# muneeb_v3.net
KiCad netlist of a schematic drawn in EAGLE
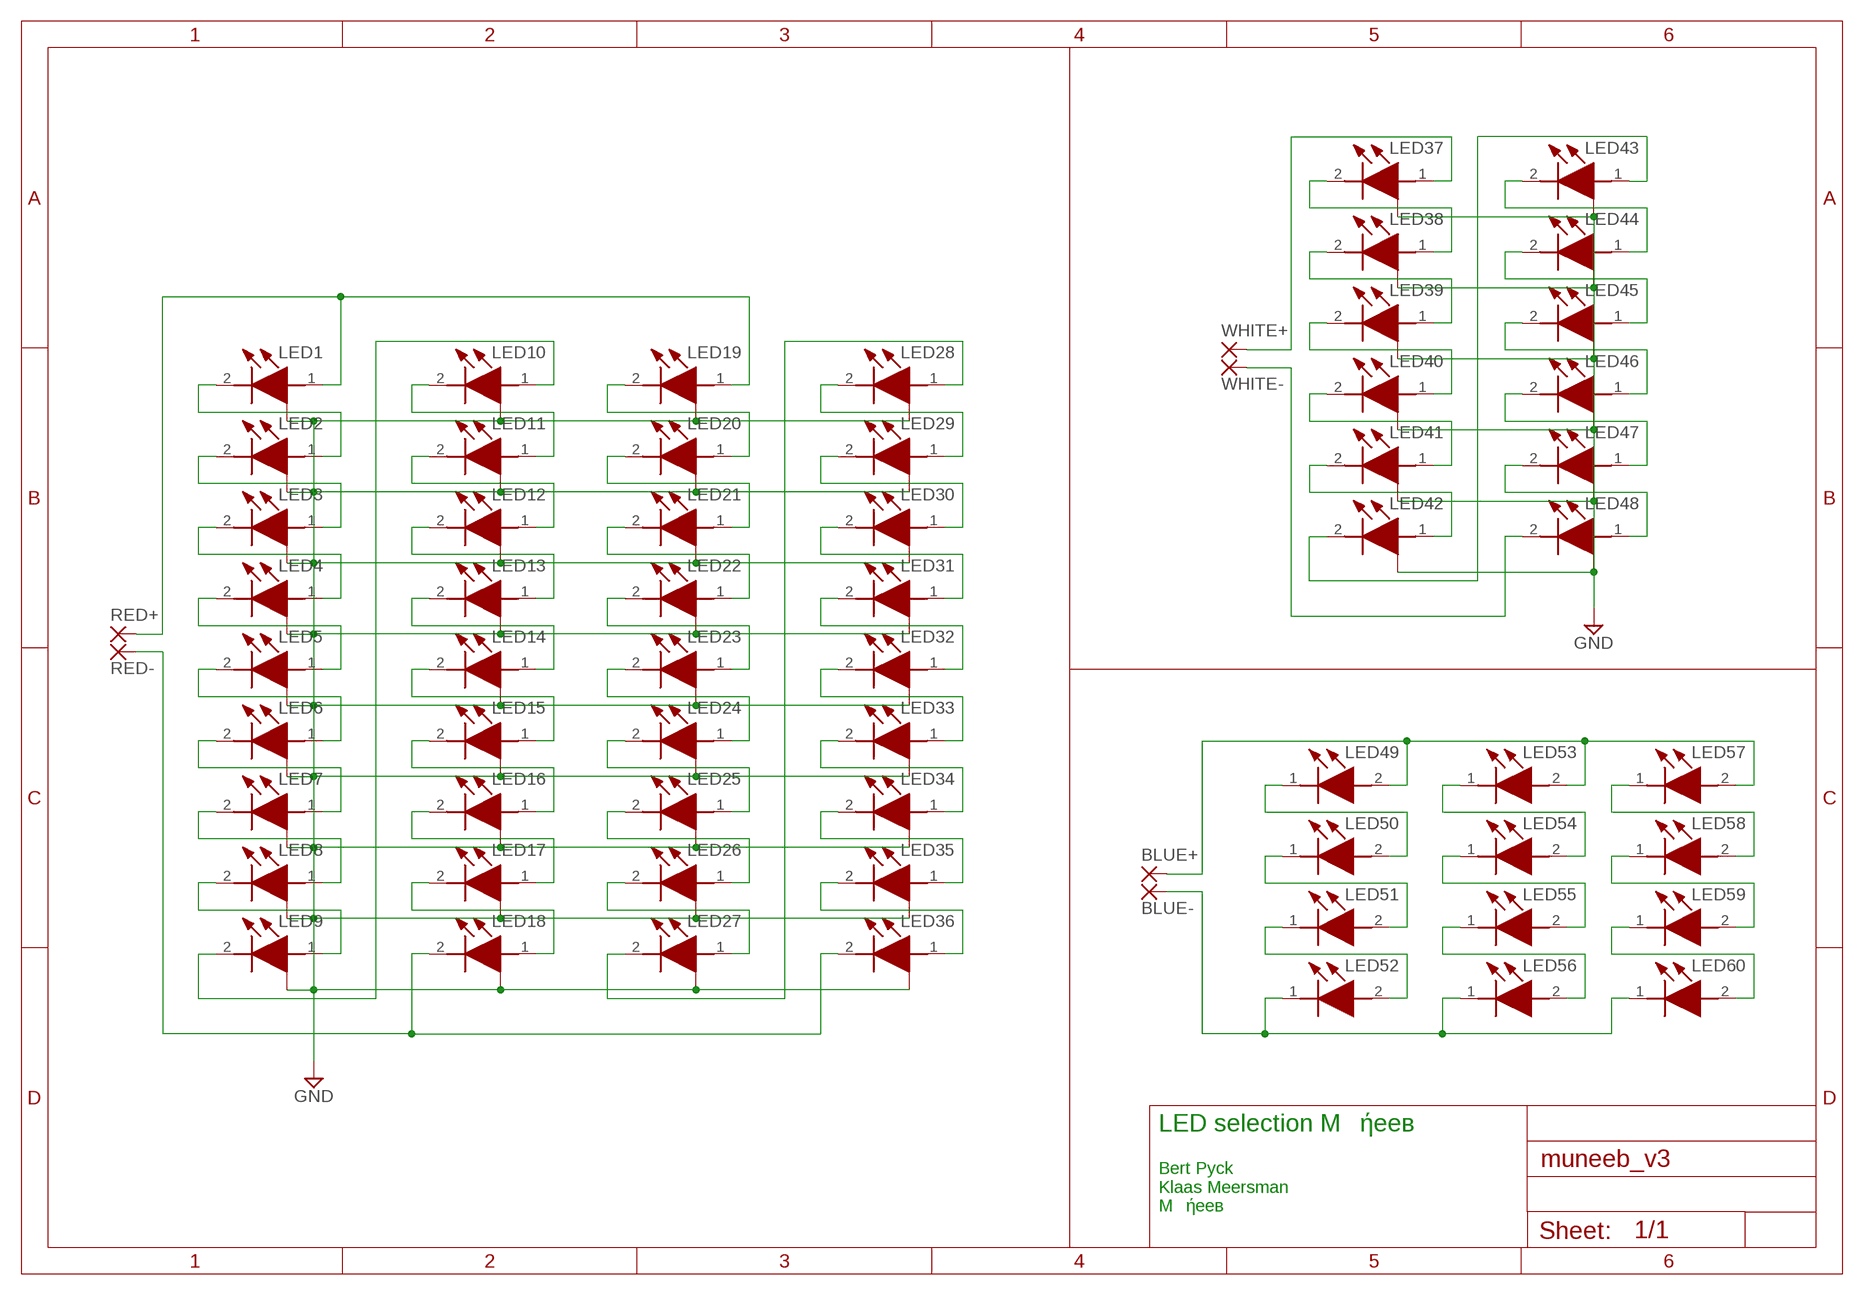
[diagram p0: schematic, sheet 1]

(export (version "E")
  (design (tool "Eeschema 10.0.6"))
  (components
    (comp (ref "BLUE+")
      (value "SOLDERPAD")
      (footprint "eagle-import:SOLDERPAD")
      (libsource (lib "eagle-import") (part "SOLDERPAD"))
    )
    (comp (ref "BLUE-")
      (value "SOLDERPAD")
      (footprint "eagle-import:SOLDERPAD")
      (libsource (lib "eagle-import") (part "SOLDERPAD"))
    )
    (comp (ref "LED1")
      (value "RED")
      (footprint "eagle-import:GR_CSSRML.24")
      (libsource (lib "eagle-import") (part "RED"))
    )
    (comp (ref "LED2")
      (value "RED")
      (footprint "eagle-import:GR_CSSRML.24")
      (libsource (lib "eagle-import") (part "RED"))
    )
    (comp (ref "LED3")
      (value "RED")
      (footprint "eagle-import:GR_CSSRML.24")
      (libsource (lib "eagle-import") (part "RED"))
    )
    (comp (ref "LED4")
      (value "RED")
      (footprint "eagle-import:GR_CSSRML.24")
      (libsource (lib "eagle-import") (part "RED"))
    )
    (comp (ref "LED5")
      (value "RED")
      (footprint "eagle-import:GR_CSSRML.24")
      (libsource (lib "eagle-import") (part "RED"))
    )
    (comp (ref "LED6")
      (value "RED")
      (footprint "eagle-import:GR_CSSRML.24")
      (libsource (lib "eagle-import") (part "RED"))
    )
    (comp (ref "LED7")
      (value "RED")
      (footprint "eagle-import:GR_CSSRML.24")
      (libsource (lib "eagle-import") (part "RED"))
    )
    (comp (ref "LED8")
      (value "RED")
      (footprint "eagle-import:GR_CSSRML.24")
      (libsource (lib "eagle-import") (part "RED"))
    )
    (comp (ref "LED9")
      (value "RED")
      (footprint "eagle-import:GR_CSSRML.24")
      (libsource (lib "eagle-import") (part "RED"))
    )
    (comp (ref "LED10")
      (value "RED")
      (footprint "eagle-import:GR_CSSRML.24")
      (libsource (lib "eagle-import") (part "RED"))
    )
    (comp (ref "LED11")
      (value "RED")
      (footprint "eagle-import:GR_CSSRML.24")
      (libsource (lib "eagle-import") (part "RED"))
    )
    (comp (ref "LED12")
      (value "RED")
      (footprint "eagle-import:GR_CSSRML.24")
      (libsource (lib "eagle-import") (part "RED"))
    )
    (comp (ref "LED13")
      (value "RED")
      (footprint "eagle-import:GR_CSSRML.24")
      (libsource (lib "eagle-import") (part "RED"))
    )
    (comp (ref "LED14")
      (value "RED")
      (footprint "eagle-import:GR_CSSRML.24")
      (libsource (lib "eagle-import") (part "RED"))
    )
    (comp (ref "LED15")
      (value "RED")
      (footprint "eagle-import:GR_CSSRML.24")
      (libsource (lib "eagle-import") (part "RED"))
    )
    (comp (ref "LED16")
      (value "RED")
      (footprint "eagle-import:GR_CSSRML.24")
      (libsource (lib "eagle-import") (part "RED"))
    )
    (comp (ref "LED17")
      (value "RED")
      (footprint "eagle-import:GR_CSSRML.24")
      (libsource (lib "eagle-import") (part "RED"))
    )
    (comp (ref "LED18")
      (value "RED")
      (footprint "eagle-import:GR_CSSRML.24")
      (libsource (lib "eagle-import") (part "RED"))
    )
    (comp (ref "LED19")
      (value "RED")
      (footprint "eagle-import:GR_CSSRML.24")
      (libsource (lib "eagle-import") (part "RED"))
    )
    (comp (ref "LED20")
      (value "RED")
      (footprint "eagle-import:GR_CSSRML.24")
      (libsource (lib "eagle-import") (part "RED"))
    )
    (comp (ref "LED21")
      (value "RED")
      (footprint "eagle-import:GR_CSSRML.24")
      (libsource (lib "eagle-import") (part "RED"))
    )
    (comp (ref "LED22")
      (value "RED")
      (footprint "eagle-import:GR_CSSRML.24")
      (libsource (lib "eagle-import") (part "RED"))
    )
    (comp (ref "LED23")
      (value "RED")
      (footprint "eagle-import:GR_CSSRML.24")
      (libsource (lib "eagle-import") (part "RED"))
    )
    (comp (ref "LED24")
      (value "RED")
      (footprint "eagle-import:GR_CSSRML.24")
      (libsource (lib "eagle-import") (part "RED"))
    )
    (comp (ref "LED25")
      (value "RED")
      (footprint "eagle-import:GR_CSSRML.24")
      (libsource (lib "eagle-import") (part "RED"))
    )
    (comp (ref "LED26")
      (value "RED")
      (footprint "eagle-import:GR_CSSRML.24")
      (libsource (lib "eagle-import") (part "RED"))
    )
    (comp (ref "LED27")
      (value "RED")
      (footprint "eagle-import:GR_CSSRML.24")
      (libsource (lib "eagle-import") (part "RED"))
    )
    (comp (ref "LED28")
      (value "RED")
      (footprint "eagle-import:GR_CSSRML.24")
      (libsource (lib "eagle-import") (part "RED"))
    )
    (comp (ref "LED29")
      (value "RED")
      (footprint "eagle-import:GR_CSSRML.24")
      (libsource (lib "eagle-import") (part "RED"))
    )
    (comp (ref "LED30")
      (value "RED")
      (footprint "eagle-import:GR_CSSRML.24")
      (libsource (lib "eagle-import") (part "RED"))
    )
    (comp (ref "LED31")
      (value "RED")
      (footprint "eagle-import:GR_CSSRML.24")
      (libsource (lib "eagle-import") (part "RED"))
    )
    (comp (ref "LED32")
      (value "RED")
      (footprint "eagle-import:GR_CSSRML.24")
      (libsource (lib "eagle-import") (part "RED"))
    )
    (comp (ref "LED33")
      (value "RED")
      (footprint "eagle-import:GR_CSSRML.24")
      (libsource (lib "eagle-import") (part "RED"))
    )
    (comp (ref "LED34")
      (value "RED")
      (footprint "eagle-import:GR_CSSRML.24")
      (libsource (lib "eagle-import") (part "RED"))
    )
    (comp (ref "LED35")
      (value "RED")
      (footprint "eagle-import:GR_CSSRML.24")
      (libsource (lib "eagle-import") (part "RED"))
    )
    (comp (ref "LED36")
      (value "RED")
      (footprint "eagle-import:GR_CSSRML.24")
      (libsource (lib "eagle-import") (part "RED"))
    )
    (comp (ref "LED37")
      (value "WHITE")
      (footprint "eagle-import:GR_CSSRML.24")
      (libsource (lib "eagle-import") (part "WHITE"))
    )
    (comp (ref "LED38")
      (value "WHITE")
      (footprint "eagle-import:GR_CSSRML.24")
      (libsource (lib "eagle-import") (part "WHITE"))
    )
    (comp (ref "LED39")
      (value "WHITE")
      (footprint "eagle-import:GR_CSSRML.24")
      (libsource (lib "eagle-import") (part "WHITE"))
    )
    (comp (ref "LED40")
      (value "WHITE")
      (footprint "eagle-import:GR_CSSRML.24")
      (libsource (lib "eagle-import") (part "WHITE"))
    )
    (comp (ref "LED41")
      (value "WHITE")
      (footprint "eagle-import:GR_CSSRML.24")
      (libsource (lib "eagle-import") (part "WHITE"))
    )
    (comp (ref "LED42")
      (value "WHITE")
      (footprint "eagle-import:GR_CSSRML.24")
      (libsource (lib "eagle-import") (part "WHITE"))
    )
    (comp (ref "LED43")
      (value "WHITE")
      (footprint "eagle-import:GR_CSSRML.24")
      (libsource (lib "eagle-import") (part "WHITE"))
    )
    (comp (ref "LED44")
      (value "WHITE")
      (footprint "eagle-import:GR_CSSRML.24")
      (libsource (lib "eagle-import") (part "WHITE"))
    )
    (comp (ref "LED45")
      (value "WHITE")
      (footprint "eagle-import:GR_CSSRML.24")
      (libsource (lib "eagle-import") (part "WHITE"))
    )
    (comp (ref "LED46")
      (value "WHITE")
      (footprint "eagle-import:GR_CSSRML.24")
      (libsource (lib "eagle-import") (part "WHITE"))
    )
    (comp (ref "LED47")
      (value "WHITE")
      (footprint "eagle-import:GR_CSSRML.24")
      (libsource (lib "eagle-import") (part "WHITE"))
    )
    (comp (ref "LED48")
      (value "WHITE")
      (footprint "eagle-import:GR_CSSRML.24")
      (libsource (lib "eagle-import") (part "WHITE"))
    )
    (comp (ref "LED49")
      (value "BLUE")
      (footprint "eagle-import:GD_JTLPSI1.14")
      (fields
        (field (name "MANUFACTURER_PART_NUMBER") "JE2835AFR-N-0001A0000-N0000001")
        (field (name "MOUSER_PART_NUMBER") "941-JE2835AFRN01AN")
      )
      (libsource (lib "eagle-import") (part "BLUE"))
    )
    (comp (ref "LED50")
      (value "BLUE")
      (footprint "eagle-import:GD_JTLPSI1.14")
      (fields
        (field (name "MANUFACTURER_PART_NUMBER") "JE2835AFR-N-0001A0000-N0000001")
        (field (name "MOUSER_PART_NUMBER") "941-JE2835AFRN01AN")
      )
      (libsource (lib "eagle-import") (part "BLUE"))
    )
    (comp (ref "LED51")
      (value "BLUE")
      (footprint "eagle-import:GD_JTLPSI1.14")
      (fields
        (field (name "MANUFACTURER_PART_NUMBER") "JE2835AFR-N-0001A0000-N0000001")
        (field (name "MOUSER_PART_NUMBER") "941-JE2835AFRN01AN")
      )
      (libsource (lib "eagle-import") (part "BLUE"))
    )
    (comp (ref "LED52")
      (value "BLUE")
      (footprint "eagle-import:GD_JTLPSI1.14")
      (fields
        (field (name "MANUFACTURER_PART_NUMBER") "JE2835AFR-N-0001A0000-N0000001")
        (field (name "MOUSER_PART_NUMBER") "941-JE2835AFRN01AN")
      )
      (libsource (lib "eagle-import") (part "BLUE"))
    )
    (comp (ref "LED53")
      (value "BLUE")
      (footprint "eagle-import:GD_JTLPSI1.14")
      (fields
        (field (name "MANUFACTURER_PART_NUMBER") "JE2835AFR-N-0001A0000-N0000001")
        (field (name "MOUSER_PART_NUMBER") "941-JE2835AFRN01AN")
      )
      (libsource (lib "eagle-import") (part "BLUE"))
    )
    (comp (ref "LED54")
      (value "BLUE")
      (footprint "eagle-import:GD_JTLPSI1.14")
      (fields
        (field (name "MANUFACTURER_PART_NUMBER") "JE2835AFR-N-0001A0000-N0000001")
        (field (name "MOUSER_PART_NUMBER") "941-JE2835AFRN01AN")
      )
      (libsource (lib "eagle-import") (part "BLUE"))
    )
    (comp (ref "LED55")
      (value "BLUE")
      (footprint "eagle-import:GD_JTLPSI1.14")
      (fields
        (field (name "MANUFACTURER_PART_NUMBER") "JE2835AFR-N-0001A0000-N0000001")
        (field (name "MOUSER_PART_NUMBER") "941-JE2835AFRN01AN")
      )
      (libsource (lib "eagle-import") (part "BLUE"))
    )
    (comp (ref "LED56")
      (value "BLUE")
      (footprint "eagle-import:GD_JTLPSI1.14")
      (fields
        (field (name "MANUFACTURER_PART_NUMBER") "JE2835AFR-N-0001A0000-N0000001")
        (field (name "MOUSER_PART_NUMBER") "941-JE2835AFRN01AN")
      )
      (libsource (lib "eagle-import") (part "BLUE"))
    )
    (comp (ref "LED57")
      (value "BLUE")
      (footprint "eagle-import:GD_JTLPSI1.14")
      (fields
        (field (name "MANUFACTURER_PART_NUMBER") "JE2835AFR-N-0001A0000-N0000001")
        (field (name "MOUSER_PART_NUMBER") "941-JE2835AFRN01AN")
      )
      (libsource (lib "eagle-import") (part "BLUE"))
    )
    (comp (ref "LED58")
      (value "BLUE")
      (footprint "eagle-import:GD_JTLPSI1.14")
      (fields
        (field (name "MANUFACTURER_PART_NUMBER") "JE2835AFR-N-0001A0000-N0000001")
        (field (name "MOUSER_PART_NUMBER") "941-JE2835AFRN01AN")
      )
      (libsource (lib "eagle-import") (part "BLUE"))
    )
    (comp (ref "LED59")
      (value "BLUE")
      (footprint "eagle-import:GD_JTLPSI1.14")
      (fields
        (field (name "MANUFACTURER_PART_NUMBER") "JE2835AFR-N-0001A0000-N0000001")
        (field (name "MOUSER_PART_NUMBER") "941-JE2835AFRN01AN")
      )
      (libsource (lib "eagle-import") (part "BLUE"))
    )
    (comp (ref "LED60")
      (value "BLUE")
      (footprint "eagle-import:GD_JTLPSI1.14")
      (fields
        (field (name "MANUFACTURER_PART_NUMBER") "JE2835AFR-N-0001A0000-N0000001")
        (field (name "MOUSER_PART_NUMBER") "941-JE2835AFRN01AN")
      )
      (libsource (lib "eagle-import") (part "BLUE"))
    )
    (comp (ref "RED+")
      (value "SOLDERPAD")
      (footprint "eagle-import:SOLDERPAD")
      (libsource (lib "eagle-import") (part "SOLDERPAD"))
    )
    (comp (ref "RED-")
      (value "SOLDERPAD")
      (footprint "eagle-import:SOLDERPAD")
      (libsource (lib "eagle-import") (part "SOLDERPAD"))
    )
    (comp (ref "WHITE+")
      (value "SOLDERPAD")
      (footprint "eagle-import:SOLDERPAD")
      (libsource (lib "eagle-import") (part "SOLDERPAD"))
    )
    (comp (ref "WHITE-")
      (value "SOLDERPAD")
      (footprint "eagle-import:SOLDERPAD")
      (libsource (lib "eagle-import") (part "SOLDERPAD"))
    )
  )
  (nets
    (net (code "1") (name "GND") (class "Default")
      (node (ref "LED1") (pin "GND") (pinfunction "GND_GND") (pintype "bidirectional"))
      (node (ref "LED1") (pin "P$1") (pinfunction "GND_P$1") (pintype "bidirectional"))
      (node (ref "LED1") (pin "P$11") (pinfunction "GND_P$11") (pintype "bidirectional"))
      (node (ref "LED1") (pin "P$12") (pinfunction "GND_P$12") (pintype "bidirectional"))
      (node (ref "LED1") (pin "P$13") (pinfunction "GND_P$13") (pintype "bidirectional"))
      (node (ref "LED1") (pin "P$14") (pinfunction "GND_P$14") (pintype "bidirectional"))
      (node (ref "LED1") (pin "P$15") (pinfunction "GND_P$15") (pintype "bidirectional"))
      (node (ref "LED1") (pin "P$3") (pinfunction "GND_P$3") (pintype "bidirectional"))
      (node (ref "LED1") (pin "P$5") (pinfunction "GND_P$5") (pintype "bidirectional"))
      (node (ref "LED1") (pin "P$6") (pinfunction "GND_P$6") (pintype "bidirectional"))
      (node (ref "LED1") (pin "P$7") (pinfunction "GND_P$7") (pintype "bidirectional"))
      (node (ref "LED1") (pin "P$8") (pinfunction "GND_P$8") (pintype "bidirectional"))
      (node (ref "LED1") (pin "P$9") (pinfunction "GND_P$9") (pintype "bidirectional"))
      (node (ref "LED10") (pin "GND") (pinfunction "GND_GND") (pintype "bidirectional"))
      (node (ref "LED10") (pin "P$1") (pinfunction "GND_P$1") (pintype "bidirectional"))
      (node (ref "LED10") (pin "P$11") (pinfunction "GND_P$11") (pintype "bidirectional"))
      (node (ref "LED10") (pin "P$12") (pinfunction "GND_P$12") (pintype "bidirectional"))
      (node (ref "LED10") (pin "P$13") (pinfunction "GND_P$13") (pintype "bidirectional"))
      (node (ref "LED10") (pin "P$14") (pinfunction "GND_P$14") (pintype "bidirectional"))
      (node (ref "LED10") (pin "P$15") (pinfunction "GND_P$15") (pintype "bidirectional"))
      (node (ref "LED10") (pin "P$3") (pinfunction "GND_P$3") (pintype "bidirectional"))
      (node (ref "LED10") (pin "P$5") (pinfunction "GND_P$5") (pintype "bidirectional"))
      (node (ref "LED10") (pin "P$6") (pinfunction "GND_P$6") (pintype "bidirectional"))
      (node (ref "LED10") (pin "P$7") (pinfunction "GND_P$7") (pintype "bidirectional"))
      (node (ref "LED10") (pin "P$8") (pinfunction "GND_P$8") (pintype "bidirectional"))
      (node (ref "LED10") (pin "P$9") (pinfunction "GND_P$9") (pintype "bidirectional"))
      (node (ref "LED11") (pin "GND") (pinfunction "GND_GND") (pintype "bidirectional"))
      (node (ref "LED11") (pin "P$1") (pinfunction "GND_P$1") (pintype "bidirectional"))
      (node (ref "LED11") (pin "P$11") (pinfunction "GND_P$11") (pintype "bidirectional"))
      (node (ref "LED11") (pin "P$12") (pinfunction "GND_P$12") (pintype "bidirectional"))
      (node (ref "LED11") (pin "P$13") (pinfunction "GND_P$13") (pintype "bidirectional"))
      (node (ref "LED11") (pin "P$14") (pinfunction "GND_P$14") (pintype "bidirectional"))
      (node (ref "LED11") (pin "P$15") (pinfunction "GND_P$15") (pintype "bidirectional"))
      (node (ref "LED11") (pin "P$3") (pinfunction "GND_P$3") (pintype "bidirectional"))
      (node (ref "LED11") (pin "P$5") (pinfunction "GND_P$5") (pintype "bidirectional"))
      (node (ref "LED11") (pin "P$6") (pinfunction "GND_P$6") (pintype "bidirectional"))
      (node (ref "LED11") (pin "P$7") (pinfunction "GND_P$7") (pintype "bidirectional"))
      (node (ref "LED11") (pin "P$8") (pinfunction "GND_P$8") (pintype "bidirectional"))
      (node (ref "LED11") (pin "P$9") (pinfunction "GND_P$9") (pintype "bidirectional"))
      (node (ref "LED12") (pin "GND") (pinfunction "GND_GND") (pintype "bidirectional"))
      (node (ref "LED12") (pin "P$1") (pinfunction "GND_P$1") (pintype "bidirectional"))
      (node (ref "LED12") (pin "P$11") (pinfunction "GND_P$11") (pintype "bidirectional"))
      (node (ref "LED12") (pin "P$12") (pinfunction "GND_P$12") (pintype "bidirectional"))
      (node (ref "LED12") (pin "P$13") (pinfunction "GND_P$13") (pintype "bidirectional"))
      (node (ref "LED12") (pin "P$14") (pinfunction "GND_P$14") (pintype "bidirectional"))
      (node (ref "LED12") (pin "P$15") (pinfunction "GND_P$15") (pintype "bidirectional"))
      (node (ref "LED12") (pin "P$3") (pinfunction "GND_P$3") (pintype "bidirectional"))
      (node (ref "LED12") (pin "P$5") (pinfunction "GND_P$5") (pintype "bidirectional"))
      (node (ref "LED12") (pin "P$6") (pinfunction "GND_P$6") (pintype "bidirectional"))
      (node (ref "LED12") (pin "P$7") (pinfunction "GND_P$7") (pintype "bidirectional"))
      (node (ref "LED12") (pin "P$8") (pinfunction "GND_P$8") (pintype "bidirectional"))
      (node (ref "LED12") (pin "P$9") (pinfunction "GND_P$9") (pintype "bidirectional"))
      (node (ref "LED13") (pin "GND") (pinfunction "GND_GND") (pintype "bidirectional"))
      (node (ref "LED13") (pin "P$1") (pinfunction "GND_P$1") (pintype "bidirectional"))
      (node (ref "LED13") (pin "P$11") (pinfunction "GND_P$11") (pintype "bidirectional"))
      (node (ref "LED13") (pin "P$12") (pinfunction "GND_P$12") (pintype "bidirectional"))
      (node (ref "LED13") (pin "P$13") (pinfunction "GND_P$13") (pintype "bidirectional"))
      (node (ref "LED13") (pin "P$14") (pinfunction "GND_P$14") (pintype "bidirectional"))
      (node (ref "LED13") (pin "P$15") (pinfunction "GND_P$15") (pintype "bidirectional"))
      (node (ref "LED13") (pin "P$3") (pinfunction "GND_P$3") (pintype "bidirectional"))
      (node (ref "LED13") (pin "P$5") (pinfunction "GND_P$5") (pintype "bidirectional"))
      (node (ref "LED13") (pin "P$6") (pinfunction "GND_P$6") (pintype "bidirectional"))
      (node (ref "LED13") (pin "P$7") (pinfunction "GND_P$7") (pintype "bidirectional"))
      (node (ref "LED13") (pin "P$8") (pinfunction "GND_P$8") (pintype "bidirectional"))
      (node (ref "LED13") (pin "P$9") (pinfunction "GND_P$9") (pintype "bidirectional"))
      (node (ref "LED14") (pin "GND") (pinfunction "GND_GND") (pintype "bidirectional"))
      (node (ref "LED14") (pin "P$1") (pinfunction "GND_P$1") (pintype "bidirectional"))
      (node (ref "LED14") (pin "P$11") (pinfunction "GND_P$11") (pintype "bidirectional"))
      (node (ref "LED14") (pin "P$12") (pinfunction "GND_P$12") (pintype "bidirectional"))
      (node (ref "LED14") (pin "P$13") (pinfunction "GND_P$13") (pintype "bidirectional"))
      (node (ref "LED14") (pin "P$14") (pinfunction "GND_P$14") (pintype "bidirectional"))
      (node (ref "LED14") (pin "P$15") (pinfunction "GND_P$15") (pintype "bidirectional"))
      (node (ref "LED14") (pin "P$3") (pinfunction "GND_P$3") (pintype "bidirectional"))
      (node (ref "LED14") (pin "P$5") (pinfunction "GND_P$5") (pintype "bidirectional"))
      (node (ref "LED14") (pin "P$6") (pinfunction "GND_P$6") (pintype "bidirectional"))
      (node (ref "LED14") (pin "P$7") (pinfunction "GND_P$7") (pintype "bidirectional"))
      (node (ref "LED14") (pin "P$8") (pinfunction "GND_P$8") (pintype "bidirectional"))
      (node (ref "LED14") (pin "P$9") (pinfunction "GND_P$9") (pintype "bidirectional"))
      (node (ref "LED15") (pin "GND") (pinfunction "GND_GND") (pintype "bidirectional"))
      (node (ref "LED15") (pin "P$1") (pinfunction "GND_P$1") (pintype "bidirectional"))
      (node (ref "LED15") (pin "P$11") (pinfunction "GND_P$11") (pintype "bidirectional"))
      (node (ref "LED15") (pin "P$12") (pinfunction "GND_P$12") (pintype "bidirectional"))
      (node (ref "LED15") (pin "P$13") (pinfunction "GND_P$13") (pintype "bidirectional"))
      (node (ref "LED15") (pin "P$14") (pinfunction "GND_P$14") (pintype "bidirectional"))
      (node (ref "LED15") (pin "P$15") (pinfunction "GND_P$15") (pintype "bidirectional"))
      (node (ref "LED15") (pin "P$3") (pinfunction "GND_P$3") (pintype "bidirectional"))
      (node (ref "LED15") (pin "P$5") (pinfunction "GND_P$5") (pintype "bidirectional"))
      (node (ref "LED15") (pin "P$6") (pinfunction "GND_P$6") (pintype "bidirectional"))
      (node (ref "LED15") (pin "P$7") (pinfunction "GND_P$7") (pintype "bidirectional"))
      (node (ref "LED15") (pin "P$8") (pinfunction "GND_P$8") (pintype "bidirectional"))
      (node (ref "LED15") (pin "P$9") (pinfunction "GND_P$9") (pintype "bidirectional"))
      (node (ref "LED16") (pin "GND") (pinfunction "GND_GND") (pintype "bidirectional"))
      (node (ref "LED16") (pin "P$1") (pinfunction "GND_P$1") (pintype "bidirectional"))
      (node (ref "LED16") (pin "P$11") (pinfunction "GND_P$11") (pintype "bidirectional"))
      (node (ref "LED16") (pin "P$12") (pinfunction "GND_P$12") (pintype "bidirectional"))
      (node (ref "LED16") (pin "P$13") (pinfunction "GND_P$13") (pintype "bidirectional"))
      (node (ref "LED16") (pin "P$14") (pinfunction "GND_P$14") (pintype "bidirectional"))
      (node (ref "LED16") (pin "P$15") (pinfunction "GND_P$15") (pintype "bidirectional"))
      (node (ref "LED16") (pin "P$3") (pinfunction "GND_P$3") (pintype "bidirectional"))
      (node (ref "LED16") (pin "P$5") (pinfunction "GND_P$5") (pintype "bidirectional"))
      (node (ref "LED16") (pin "P$6") (pinfunction "GND_P$6") (pintype "bidirectional"))
      (node (ref "LED16") (pin "P$7") (pinfunction "GND_P$7") (pintype "bidirectional"))
      (node (ref "LED16") (pin "P$8") (pinfunction "GND_P$8") (pintype "bidirectional"))
      (node (ref "LED16") (pin "P$9") (pinfunction "GND_P$9") (pintype "bidirectional"))
      (node (ref "LED17") (pin "GND") (pinfunction "GND_GND") (pintype "bidirectional"))
      (node (ref "LED17") (pin "P$1") (pinfunction "GND_P$1") (pintype "bidirectional"))
      (node (ref "LED17") (pin "P$11") (pinfunction "GND_P$11") (pintype "bidirectional"))
      (node (ref "LED17") (pin "P$12") (pinfunction "GND_P$12") (pintype "bidirectional"))
      (node (ref "LED17") (pin "P$13") (pinfunction "GND_P$13") (pintype "bidirectional"))
      (node (ref "LED17") (pin "P$14") (pinfunction "GND_P$14") (pintype "bidirectional"))
      (node (ref "LED17") (pin "P$15") (pinfunction "GND_P$15") (pintype "bidirectional"))
      (node (ref "LED17") (pin "P$3") (pinfunction "GND_P$3") (pintype "bidirectional"))
      (node (ref "LED17") (pin "P$5") (pinfunction "GND_P$5") (pintype "bidirectional"))
      (node (ref "LED17") (pin "P$6") (pinfunction "GND_P$6") (pintype "bidirectional"))
      (node (ref "LED17") (pin "P$7") (pinfunction "GND_P$7") (pintype "bidirectional"))
      (node (ref "LED17") (pin "P$8") (pinfunction "GND_P$8") (pintype "bidirectional"))
      (node (ref "LED17") (pin "P$9") (pinfunction "GND_P$9") (pintype "bidirectional"))
      (node (ref "LED18") (pin "GND") (pinfunction "GND_GND") (pintype "bidirectional"))
      (node (ref "LED18") (pin "P$1") (pinfunction "GND_P$1") (pintype "bidirectional"))
      (node (ref "LED18") (pin "P$11") (pinfunction "GND_P$11") (pintype "bidirectional"))
      (node (ref "LED18") (pin "P$12") (pinfunction "GND_P$12") (pintype "bidirectional"))
      (node (ref "LED18") (pin "P$13") (pinfunction "GND_P$13") (pintype "bidirectional"))
      (node (ref "LED18") (pin "P$14") (pinfunction "GND_P$14") (pintype "bidirectional"))
      (node (ref "LED18") (pin "P$15") (pinfunction "GND_P$15") (pintype "bidirectional"))
      (node (ref "LED18") (pin "P$3") (pinfunction "GND_P$3") (pintype "bidirectional"))
      (node (ref "LED18") (pin "P$5") (pinfunction "GND_P$5") (pintype "bidirectional"))
      (node (ref "LED18") (pin "P$6") (pinfunction "GND_P$6") (pintype "bidirectional"))
      (node (ref "LED18") (pin "P$7") (pinfunction "GND_P$7") (pintype "bidirectional"))
      (node (ref "LED18") (pin "P$8") (pinfunction "GND_P$8") (pintype "bidirectional"))
      (node (ref "LED18") (pin "P$9") (pinfunction "GND_P$9") (pintype "bidirectional"))
      (node (ref "LED19") (pin "GND") (pinfunction "GND_GND") (pintype "bidirectional"))
      (node (ref "LED19") (pin "P$1") (pinfunction "GND_P$1") (pintype "bidirectional"))
      (node (ref "LED19") (pin "P$11") (pinfunction "GND_P$11") (pintype "bidirectional"))
      (node (ref "LED19") (pin "P$12") (pinfunction "GND_P$12") (pintype "bidirectional"))
      (node (ref "LED19") (pin "P$13") (pinfunction "GND_P$13") (pintype "bidirectional"))
      (node (ref "LED19") (pin "P$14") (pinfunction "GND_P$14") (pintype "bidirectional"))
      (node (ref "LED19") (pin "P$15") (pinfunction "GND_P$15") (pintype "bidirectional"))
      (node (ref "LED19") (pin "P$3") (pinfunction "GND_P$3") (pintype "bidirectional"))
      (node (ref "LED19") (pin "P$5") (pinfunction "GND_P$5") (pintype "bidirectional"))
      (node (ref "LED19") (pin "P$6") (pinfunction "GND_P$6") (pintype "bidirectional"))
      (node (ref "LED19") (pin "P$7") (pinfunction "GND_P$7") (pintype "bidirectional"))
      (node (ref "LED19") (pin "P$8") (pinfunction "GND_P$8") (pintype "bidirectional"))
      (node (ref "LED19") (pin "P$9") (pinfunction "GND_P$9") (pintype "bidirectional"))
      (node (ref "LED2") (pin "GND") (pinfunction "GND_GND") (pintype "bidirectional"))
      (node (ref "LED2") (pin "P$1") (pinfunction "GND_P$1") (pintype "bidirectional"))
      (node (ref "LED2") (pin "P$11") (pinfunction "GND_P$11") (pintype "bidirectional"))
      (node (ref "LED2") (pin "P$12") (pinfunction "GND_P$12") (pintype "bidirectional"))
      (node (ref "LED2") (pin "P$13") (pinfunction "GND_P$13") (pintype "bidirectional"))
      (node (ref "LED2") (pin "P$14") (pinfunction "GND_P$14") (pintype "bidirectional"))
      (node (ref "LED2") (pin "P$15") (pinfunction "GND_P$15") (pintype "bidirectional"))
      (node (ref "LED2") (pin "P$3") (pinfunction "GND_P$3") (pintype "bidirectional"))
      (node (ref "LED2") (pin "P$5") (pinfunction "GND_P$5") (pintype "bidirectional"))
      (node (ref "LED2") (pin "P$6") (pinfunction "GND_P$6") (pintype "bidirectional"))
      (node (ref "LED2") (pin "P$7") (pinfunction "GND_P$7") (pintype "bidirectional"))
      (node (ref "LED2") (pin "P$8") (pinfunction "GND_P$8") (pintype "bidirectional"))
      (node (ref "LED2") (pin "P$9") (pinfunction "GND_P$9") (pintype "bidirectional"))
      (node (ref "LED20") (pin "GND") (pinfunction "GND_GND") (pintype "bidirectional"))
      (node (ref "LED20") (pin "P$1") (pinfunction "GND_P$1") (pintype "bidirectional"))
      (node (ref "LED20") (pin "P$11") (pinfunction "GND_P$11") (pintype "bidirectional"))
      (node (ref "LED20") (pin "P$12") (pinfunction "GND_P$12") (pintype "bidirectional"))
      (node (ref "LED20") (pin "P$13") (pinfunction "GND_P$13") (pintype "bidirectional"))
      (node (ref "LED20") (pin "P$14") (pinfunction "GND_P$14") (pintype "bidirectional"))
      (node (ref "LED20") (pin "P$15") (pinfunction "GND_P$15") (pintype "bidirectional"))
      (node (ref "LED20") (pin "P$3") (pinfunction "GND_P$3") (pintype "bidirectional"))
      (node (ref "LED20") (pin "P$5") (pinfunction "GND_P$5") (pintype "bidirectional"))
      (node (ref "LED20") (pin "P$6") (pinfunction "GND_P$6") (pintype "bidirectional"))
      (node (ref "LED20") (pin "P$7") (pinfunction "GND_P$7") (pintype "bidirectional"))
      (node (ref "LED20") (pin "P$8") (pinfunction "GND_P$8") (pintype "bidirectional"))
      (node (ref "LED20") (pin "P$9") (pinfunction "GND_P$9") (pintype "bidirectional"))
      (node (ref "LED21") (pin "GND") (pinfunction "GND_GND") (pintype "bidirectional"))
      (node (ref "LED21") (pin "P$1") (pinfunction "GND_P$1") (pintype "bidirectional"))
      (node (ref "LED21") (pin "P$11") (pinfunction "GND_P$11") (pintype "bidirectional"))
      (node (ref "LED21") (pin "P$12") (pinfunction "GND_P$12") (pintype "bidirectional"))
      (node (ref "LED21") (pin "P$13") (pinfunction "GND_P$13") (pintype "bidirectional"))
      (node (ref "LED21") (pin "P$14") (pinfunction "GND_P$14") (pintype "bidirectional"))
      (node (ref "LED21") (pin "P$15") (pinfunction "GND_P$15") (pintype "bidirectional"))
      (node (ref "LED21") (pin "P$3") (pinfunction "GND_P$3") (pintype "bidirectional"))
      (node (ref "LED21") (pin "P$5") (pinfunction "GND_P$5") (pintype "bidirectional"))
      (node (ref "LED21") (pin "P$6") (pinfunction "GND_P$6") (pintype "bidirectional"))
      (node (ref "LED21") (pin "P$7") (pinfunction "GND_P$7") (pintype "bidirectional"))
      (node (ref "LED21") (pin "P$8") (pinfunction "GND_P$8") (pintype "bidirectional"))
      (node (ref "LED21") (pin "P$9") (pinfunction "GND_P$9") (pintype "bidirectional"))
      (node (ref "LED22") (pin "GND") (pinfunction "GND_GND") (pintype "bidirectional"))
      (node (ref "LED22") (pin "P$1") (pinfunction "GND_P$1") (pintype "bidirectional"))
      (node (ref "LED22") (pin "P$11") (pinfunction "GND_P$11") (pintype "bidirectional"))
      (node (ref "LED22") (pin "P$12") (pinfunction "GND_P$12") (pintype "bidirectional"))
      (node (ref "LED22") (pin "P$13") (pinfunction "GND_P$13") (pintype "bidirectional"))
      (node (ref "LED22") (pin "P$14") (pinfunction "GND_P$14") (pintype "bidirectional"))
      (node (ref "LED22") (pin "P$15") (pinfunction "GND_P$15") (pintype "bidirectional"))
      (node (ref "LED22") (pin "P$3") (pinfunction "GND_P$3") (pintype "bidirectional"))
      (node (ref "LED22") (pin "P$5") (pinfunction "GND_P$5") (pintype "bidirectional"))
      (node (ref "LED22") (pin "P$6") (pinfunction "GND_P$6") (pintype "bidirectional"))
      (node (ref "LED22") (pin "P$7") (pinfunction "GND_P$7") (pintype "bidirectional"))
      (node (ref "LED22") (pin "P$8") (pinfunction "GND_P$8") (pintype "bidirectional"))
      (node (ref "LED22") (pin "P$9") (pinfunction "GND_P$9") (pintype "bidirectional"))
      (node (ref "LED23") (pin "GND") (pinfunction "GND_GND") (pintype "bidirectional"))
      (node (ref "LED23") (pin "P$1") (pinfunction "GND_P$1") (pintype "bidirectional"))
      (node (ref "LED23") (pin "P$11") (pinfunction "GND_P$11") (pintype "bidirectional"))
      (node (ref "LED23") (pin "P$12") (pinfunction "GND_P$12") (pintype "bidirectional"))
      (node (ref "LED23") (pin "P$13") (pinfunction "GND_P$13") (pintype "bidirectional"))
      (node (ref "LED23") (pin "P$14") (pinfunction "GND_P$14") (pintype "bidirectional"))
      (node (ref "LED23") (pin "P$15") (pinfunction "GND_P$15") (pintype "bidirectional"))
      (node (ref "LED23") (pin "P$3") (pinfunction "GND_P$3") (pintype "bidirectional"))
      (node (ref "LED23") (pin "P$5") (pinfunction "GND_P$5") (pintype "bidirectional"))
      (node (ref "LED23") (pin "P$6") (pinfunction "GND_P$6") (pintype "bidirectional"))
      (node (ref "LED23") (pin "P$7") (pinfunction "GND_P$7") (pintype "bidirectional"))
      (node (ref "LED23") (pin "P$8") (pinfunction "GND_P$8") (pintype "bidirectional"))
      (node (ref "LED23") (pin "P$9") (pinfunction "GND_P$9") (pintype "bidirectional"))
      (node (ref "LED24") (pin "GND") (pinfunction "GND_GND") (pintype "bidirectional"))
      (node (ref "LED24") (pin "P$1") (pinfunction "GND_P$1") (pintype "bidirectional"))
      (node (ref "LED24") (pin "P$11") (pinfunction "GND_P$11") (pintype "bidirectional"))
      (node (ref "LED24") (pin "P$12") (pinfunction "GND_P$12") (pintype "bidirectional"))
      (node (ref "LED24") (pin "P$13") (pinfunction "GND_P$13") (pintype "bidirectional"))
      (node (ref "LED24") (pin "P$14") (pinfunction "GND_P$14") (pintype "bidirectional"))
      (node (ref "LED24") (pin "P$15") (pinfunction "GND_P$15") (pintype "bidirectional"))
      (node (ref "LED24") (pin "P$3") (pinfunction "GND_P$3") (pintype "bidirectional"))
      (node (ref "LED24") (pin "P$5") (pinfunction "GND_P$5") (pintype "bidirectional"))
      (node (ref "LED24") (pin "P$6") (pinfunction "GND_P$6") (pintype "bidirectional"))
      (node (ref "LED24") (pin "P$7") (pinfunction "GND_P$7") (pintype "bidirectional"))
      (node (ref "LED24") (pin "P$8") (pinfunction "GND_P$8") (pintype "bidirectional"))
      (node (ref "LED24") (pin "P$9") (pinfunction "GND_P$9") (pintype "bidirectional"))
      (node (ref "LED25") (pin "GND") (pinfunction "GND_GND") (pintype "bidirectional"))
      (node (ref "LED25") (pin "P$1") (pinfunction "GND_P$1") (pintype "bidirectional"))
      (node (ref "LED25") (pin "P$11") (pinfunction "GND_P$11") (pintype "bidirectional"))
      (node (ref "LED25") (pin "P$12") (pinfunction "GND_P$12") (pintype "bidirectional"))
      (node (ref "LED25") (pin "P$13") (pinfunction "GND_P$13") (pintype "bidirectional"))
      (node (ref "LED25") (pin "P$14") (pinfunction "GND_P$14") (pintype "bidirectional"))
      (node (ref "LED25") (pin "P$15") (pinfunction "GND_P$15") (pintype "bidirectional"))
      (node (ref "LED25") (pin "P$3") (pinfunction "GND_P$3") (pintype "bidirectional"))
      (node (ref "LED25") (pin "P$5") (pinfunction "GND_P$5") (pintype "bidirectional"))
      (node (ref "LED25") (pin "P$6") (pinfunction "GND_P$6") (pintype "bidirectional"))
      (node (ref "LED25") (pin "P$7") (pinfunction "GND_P$7") (pintype "bidirectional"))
      (node (ref "LED25") (pin "P$8") (pinfunction "GND_P$8") (pintype "bidirectional"))
      (node (ref "LED25") (pin "P$9") (pinfunction "GND_P$9") (pintype "bidirectional"))
      (node (ref "LED26") (pin "GND") (pinfunction "GND_GND") (pintype "bidirectional"))
      (node (ref "LED26") (pin "P$1") (pinfunction "GND_P$1") (pintype "bidirectional"))
      (node (ref "LED26") (pin "P$11") (pinfunction "GND_P$11") (pintype "bidirectional"))
      (node (ref "LED26") (pin "P$12") (pinfunction "GND_P$12") (pintype "bidirectional"))
      (node (ref "LED26") (pin "P$13") (pinfunction "GND_P$13") (pintype "bidirectional"))
      (node (ref "LED26") (pin "P$14") (pinfunction "GND_P$14") (pintype "bidirectional"))
      (node (ref "LED26") (pin "P$15") (pinfunction "GND_P$15") (pintype "bidirectional"))
      (node (ref "LED26") (pin "P$3") (pinfunction "GND_P$3") (pintype "bidirectional"))
      (node (ref "LED26") (pin "P$5") (pinfunction "GND_P$5") (pintype "bidirectional"))
      (node (ref "LED26") (pin "P$6") (pinfunction "GND_P$6") (pintype "bidirectional"))
      (node (ref "LED26") (pin "P$7") (pinfunction "GND_P$7") (pintype "bidirectional"))
      (node (ref "LED26") (pin "P$8") (pinfunction "GND_P$8") (pintype "bidirectional"))
      (node (ref "LED26") (pin "P$9") (pinfunction "GND_P$9") (pintype "bidirectional"))
      (node (ref "LED27") (pin "GND") (pinfunction "GND_GND") (pintype "bidirectional"))
      (node (ref "LED27") (pin "P$1") (pinfunction "GND_P$1") (pintype "bidirectional"))
      (node (ref "LED27") (pin "P$11") (pinfunction "GND_P$11") (pintype "bidirectional"))
      (node (ref "LED27") (pin "P$12") (pinfunction "GND_P$12") (pintype "bidirectional"))
      (node (ref "LED27") (pin "P$13") (pinfunction "GND_P$13") (pintype "bidirectional"))
      (node (ref "LED27") (pin "P$14") (pinfunction "GND_P$14") (pintype "bidirectional"))
      (node (ref "LED27") (pin "P$15") (pinfunction "GND_P$15") (pintype "bidirectional"))
      (node (ref "LED27") (pin "P$3") (pinfunction "GND_P$3") (pintype "bidirectional"))
      (node (ref "LED27") (pin "P$5") (pinfunction "GND_P$5") (pintype "bidirectional"))
      (node (ref "LED27") (pin "P$6") (pinfunction "GND_P$6") (pintype "bidirectional"))
      (node (ref "LED27") (pin "P$7") (pinfunction "GND_P$7") (pintype "bidirectional"))
      (node (ref "LED27") (pin "P$8") (pinfunction "GND_P$8") (pintype "bidirectional"))
      (node (ref "LED27") (pin "P$9") (pinfunction "GND_P$9") (pintype "bidirectional"))
      (node (ref "LED28") (pin "GND") (pinfunction "GND_GND") (pintype "bidirectional"))
      (node (ref "LED28") (pin "P$1") (pinfunction "GND_P$1") (pintype "bidirectional"))
      (node (ref "LED28") (pin "P$11") (pinfunction "GND_P$11") (pintype "bidirectional"))
      (node (ref "LED28") (pin "P$12") (pinfunction "GND_P$12") (pintype "bidirectional"))
      (node (ref "LED28") (pin "P$13") (pinfunction "GND_P$13") (pintype "bidirectional"))
      (node (ref "LED28") (pin "P$14") (pinfunction "GND_P$14") (pintype "bidirectional"))
      (node (ref "LED28") (pin "P$15") (pinfunction "GND_P$15") (pintype "bidirectional"))
      (node (ref "LED28") (pin "P$3") (pinfunction "GND_P$3") (pintype "bidirectional"))
      (node (ref "LED28") (pin "P$5") (pinfunction "GND_P$5") (pintype "bidirectional"))
      (node (ref "LED28") (pin "P$6") (pinfunction "GND_P$6") (pintype "bidirectional"))
      (node (ref "LED28") (pin "P$7") (pinfunction "GND_P$7") (pintype "bidirectional"))
      (node (ref "LED28") (pin "P$8") (pinfunction "GND_P$8") (pintype "bidirectional"))
      (node (ref "LED28") (pin "P$9") (pinfunction "GND_P$9") (pintype "bidirectional"))
      (node (ref "LED29") (pin "GND") (pinfunction "GND_GND") (pintype "bidirectional"))
      (node (ref "LED29") (pin "P$1") (pinfunction "GND_P$1") (pintype "bidirectional"))
      (node (ref "LED29") (pin "P$11") (pinfunction "GND_P$11") (pintype "bidirectional"))
      (node (ref "LED29") (pin "P$12") (pinfunction "GND_P$12") (pintype "bidirectional"))
      (node (ref "LED29") (pin "P$13") (pinfunction "GND_P$13") (pintype "bidirectional"))
      (node (ref "LED29") (pin "P$14") (pinfunction "GND_P$14") (pintype "bidirectional"))
      (node (ref "LED29") (pin "P$15") (pinfunction "GND_P$15") (pintype "bidirectional"))
      (node (ref "LED29") (pin "P$3") (pinfunction "GND_P$3") (pintype "bidirectional"))
      (node (ref "LED29") (pin "P$5") (pinfunction "GND_P$5") (pintype "bidirectional"))
      (node (ref "LED29") (pin "P$6") (pinfunction "GND_P$6") (pintype "bidirectional"))
      (node (ref "LED29") (pin "P$7") (pinfunction "GND_P$7") (pintype "bidirectional"))
      (node (ref "LED29") (pin "P$8") (pinfunction "GND_P$8") (pintype "bidirectional"))
      (node (ref "LED29") (pin "P$9") (pinfunction "GND_P$9") (pintype "bidirectional"))
      (node (ref "LED3") (pin "GND") (pinfunction "GND_GND") (pintype "bidirectional"))
      (node (ref "LED3") (pin "P$1") (pinfunction "GND_P$1") (pintype "bidirectional"))
      (node (ref "LED3") (pin "P$11") (pinfunction "GND_P$11") (pintype "bidirectional"))
      (node (ref "LED3") (pin "P$12") (pinfunction "GND_P$12") (pintype "bidirectional"))
      (node (ref "LED3") (pin "P$13") (pinfunction "GND_P$13") (pintype "bidirectional"))
      (node (ref "LED3") (pin "P$14") (pinfunction "GND_P$14") (pintype "bidirectional"))
      (node (ref "LED3") (pin "P$15") (pinfunction "GND_P$15") (pintype "bidirectional"))
      (node (ref "LED3") (pin "P$3") (pinfunction "GND_P$3") (pintype "bidirectional"))
      (node (ref "LED3") (pin "P$5") (pinfunction "GND_P$5") (pintype "bidirectional"))
      (node (ref "LED3") (pin "P$6") (pinfunction "GND_P$6") (pintype "bidirectional"))
      (node (ref "LED3") (pin "P$7") (pinfunction "GND_P$7") (pintype "bidirectional"))
      (node (ref "LED3") (pin "P$8") (pinfunction "GND_P$8") (pintype "bidirectional"))
      (node (ref "LED3") (pin "P$9") (pinfunction "GND_P$9") (pintype "bidirectional"))
      (node (ref "LED30") (pin "GND") (pinfunction "GND_GND") (pintype "bidirectional"))
      (node (ref "LED30") (pin "P$1") (pinfunction "GND_P$1") (pintype "bidirectional"))
      (node (ref "LED30") (pin "P$11") (pinfunction "GND_P$11") (pintype "bidirectional"))
      (node (ref "LED30") (pin "P$12") (pinfunction "GND_P$12") (pintype "bidirectional"))
      (node (ref "LED30") (pin "P$13") (pinfunction "GND_P$13") (pintype "bidirectional"))
      (node (ref "LED30") (pin "P$14") (pinfunction "GND_P$14") (pintype "bidirectional"))
      (node (ref "LED30") (pin "P$15") (pinfunction "GND_P$15") (pintype "bidirectional"))
      (node (ref "LED30") (pin "P$3") (pinfunction "GND_P$3") (pintype "bidirectional"))
      (node (ref "LED30") (pin "P$5") (pinfunction "GND_P$5") (pintype "bidirectional"))
      (node (ref "LED30") (pin "P$6") (pinfunction "GND_P$6") (pintype "bidirectional"))
      (node (ref "LED30") (pin "P$7") (pinfunction "GND_P$7") (pintype "bidirectional"))
      (node (ref "LED30") (pin "P$8") (pinfunction "GND_P$8") (pintype "bidirectional"))
      (node (ref "LED30") (pin "P$9") (pinfunction "GND_P$9") (pintype "bidirectional"))
      (node (ref "LED31") (pin "GND") (pinfunction "GND_GND") (pintype "bidirectional"))
      (node (ref "LED31") (pin "P$1") (pinfunction "GND_P$1") (pintype "bidirectional"))
      (node (ref "LED31") (pin "P$11") (pinfunction "GND_P$11") (pintype "bidirectional"))
      (node (ref "LED31") (pin "P$12") (pinfunction "GND_P$12") (pintype "bidirectional"))
      (node (ref "LED31") (pin "P$13") (pinfunction "GND_P$13") (pintype "bidirectional"))
      (node (ref "LED31") (pin "P$14") (pinfunction "GND_P$14") (pintype "bidirectional"))
      (node (ref "LED31") (pin "P$15") (pinfunction "GND_P$15") (pintype "bidirectional"))
      (node (ref "LED31") (pin "P$3") (pinfunction "GND_P$3") (pintype "bidirectional"))
      (node (ref "LED31") (pin "P$5") (pinfunction "GND_P$5") (pintype "bidirectional"))
      (node (ref "LED31") (pin "P$6") (pinfunction "GND_P$6") (pintype "bidirectional"))
      (node (ref "LED31") (pin "P$7") (pinfunction "GND_P$7") (pintype "bidirectional"))
      (node (ref "LED31") (pin "P$8") (pinfunction "GND_P$8") (pintype "bidirectional"))
      (node (ref "LED31") (pin "P$9") (pinfunction "GND_P$9") (pintype "bidirectional"))
      (node (ref "LED32") (pin "GND") (pinfunction "GND_GND") (pintype "bidirectional"))
      (node (ref "LED32") (pin "P$1") (pinfunction "GND_P$1") (pintype "bidirectional"))
      (node (ref "LED32") (pin "P$11") (pinfunction "GND_P$11") (pintype "bidirectional"))
      (node (ref "LED32") (pin "P$12") (pinfunction "GND_P$12") (pintype "bidirectional"))
      (node (ref "LED32") (pin "P$13") (pinfunction "GND_P$13") (pintype "bidirectional"))
      (node (ref "LED32") (pin "P$14") (pinfunction "GND_P$14") (pintype "bidirectional"))
      (node (ref "LED32") (pin "P$15") (pinfunction "GND_P$15") (pintype "bidirectional"))
      (node (ref "LED32") (pin "P$3") (pinfunction "GND_P$3") (pintype "bidirectional"))
      (node (ref "LED32") (pin "P$5") (pinfunction "GND_P$5") (pintype "bidirectional"))
      (node (ref "LED32") (pin "P$6") (pinfunction "GND_P$6") (pintype "bidirectional"))
      (node (ref "LED32") (pin "P$7") (pinfunction "GND_P$7") (pintype "bidirectional"))
      (node (ref "LED32") (pin "P$8") (pinfunction "GND_P$8") (pintype "bidirectional"))
      (node (ref "LED32") (pin "P$9") (pinfunction "GND_P$9") (pintype "bidirectional"))
      (node (ref "LED33") (pin "GND") (pinfunction "GND_GND") (pintype "bidirectional"))
      (node (ref "LED33") (pin "P$1") (pinfunction "GND_P$1") (pintype "bidirectional"))
      (node (ref "LED33") (pin "P$11") (pinfunction "GND_P$11") (pintype "bidirectional"))
      (node (ref "LED33") (pin "P$12") (pinfunction "GND_P$12") (pintype "bidirectional"))
      (node (ref "LED33") (pin "P$13") (pinfunction "GND_P$13") (pintype "bidirectional"))
      (node (ref "LED33") (pin "P$14") (pinfunction "GND_P$14") (pintype "bidirectional"))
      (node (ref "LED33") (pin "P$15") (pinfunction "GND_P$15") (pintype "bidirectional"))
      (node (ref "LED33") (pin "P$3") (pinfunction "GND_P$3") (pintype "bidirectional"))
      (node (ref "LED33") (pin "P$5") (pinfunction "GND_P$5") (pintype "bidirectional"))
      (node (ref "LED33") (pin "P$6") (pinfunction "GND_P$6") (pintype "bidirectional"))
      (node (ref "LED33") (pin "P$7") (pinfunction "GND_P$7") (pintype "bidirectional"))
      (node (ref "LED33") (pin "P$8") (pinfunction "GND_P$8") (pintype "bidirectional"))
      (node (ref "LED33") (pin "P$9") (pinfunction "GND_P$9") (pintype "bidirectional"))
      (node (ref "LED34") (pin "GND") (pinfunction "GND_GND") (pintype "bidirectional"))
      (node (ref "LED34") (pin "P$1") (pinfunction "GND_P$1") (pintype "bidirectional"))
      (node (ref "LED34") (pin "P$11") (pinfunction "GND_P$11") (pintype "bidirectional"))
      (node (ref "LED34") (pin "P$12") (pinfunction "GND_P$12") (pintype "bidirectional"))
      (node (ref "LED34") (pin "P$13") (pinfunction "GND_P$13") (pintype "bidirectional"))
      (node (ref "LED34") (pin "P$14") (pinfunction "GND_P$14") (pintype "bidirectional"))
      (node (ref "LED34") (pin "P$15") (pinfunction "GND_P$15") (pintype "bidirectional"))
      (node (ref "LED34") (pin "P$3") (pinfunction "GND_P$3") (pintype "bidirectional"))
      (node (ref "LED34") (pin "P$5") (pinfunction "GND_P$5") (pintype "bidirectional"))
      (node (ref "LED34") (pin "P$6") (pinfunction "GND_P$6") (pintype "bidirectional"))
      (node (ref "LED34") (pin "P$7") (pinfunction "GND_P$7") (pintype "bidirectional"))
      (node (ref "LED34") (pin "P$8") (pinfunction "GND_P$8") (pintype "bidirectional"))
      (node (ref "LED34") (pin "P$9") (pinfunction "GND_P$9") (pintype "bidirectional"))
      (node (ref "LED35") (pin "GND") (pinfunction "GND_GND") (pintype "bidirectional"))
      (node (ref "LED35") (pin "P$1") (pinfunction "GND_P$1") (pintype "bidirectional"))
      (node (ref "LED35") (pin "P$11") (pinfunction "GND_P$11") (pintype "bidirectional"))
      (node (ref "LED35") (pin "P$12") (pinfunction "GND_P$12") (pintype "bidirectional"))
      (node (ref "LED35") (pin "P$13") (pinfunction "GND_P$13") (pintype "bidirectional"))
      (node (ref "LED35") (pin "P$14") (pinfunction "GND_P$14") (pintype "bidirectional"))
      (node (ref "LED35") (pin "P$15") (pinfunction "GND_P$15") (pintype "bidirectional"))
      (node (ref "LED35") (pin "P$3") (pinfunction "GND_P$3") (pintype "bidirectional"))
      (node (ref "LED35") (pin "P$5") (pinfunction "GND_P$5") (pintype "bidirectional"))
      (node (ref "LED35") (pin "P$6") (pinfunction "GND_P$6") (pintype "bidirectional"))
      (node (ref "LED35") (pin "P$7") (pinfunction "GND_P$7") (pintype "bidirectional"))
      (node (ref "LED35") (pin "P$8") (pinfunction "GND_P$8") (pintype "bidirectional"))
      (node (ref "LED35") (pin "P$9") (pinfunction "GND_P$9") (pintype "bidirectional"))
      (node (ref "LED36") (pin "GND") (pinfunction "GND_GND") (pintype "bidirectional"))
      (node (ref "LED36") (pin "P$1") (pinfunction "GND_P$1") (pintype "bidirectional"))
      (node (ref "LED36") (pin "P$11") (pinfunction "GND_P$11") (pintype "bidirectional"))
      (node (ref "LED36") (pin "P$12") (pinfunction "GND_P$12") (pintype "bidirectional"))
      (node (ref "LED36") (pin "P$13") (pinfunction "GND_P$13") (pintype "bidirectional"))
      (node (ref "LED36") (pin "P$14") (pinfunction "GND_P$14") (pintype "bidirectional"))
      (node (ref "LED36") (pin "P$15") (pinfunction "GND_P$15") (pintype "bidirectional"))
      (node (ref "LED36") (pin "P$3") (pinfunction "GND_P$3") (pintype "bidirectional"))
      (node (ref "LED36") (pin "P$5") (pinfunction "GND_P$5") (pintype "bidirectional"))
      (node (ref "LED36") (pin "P$6") (pinfunction "GND_P$6") (pintype "bidirectional"))
      (node (ref "LED36") (pin "P$7") (pinfunction "GND_P$7") (pintype "bidirectional"))
      (node (ref "LED36") (pin "P$8") (pinfunction "GND_P$8") (pintype "bidirectional"))
      (node (ref "LED36") (pin "P$9") (pinfunction "GND_P$9") (pintype "bidirectional"))
      (node (ref "LED37") (pin "GND") (pinfunction "GND_GND") (pintype "bidirectional"))
      (node (ref "LED37") (pin "P$1") (pinfunction "GND_P$1") (pintype "bidirectional"))
      (node (ref "LED37") (pin "P$11") (pinfunction "GND_P$11") (pintype "bidirectional"))
      (node (ref "LED37") (pin "P$12") (pinfunction "GND_P$12") (pintype "bidirectional"))
      (node (ref "LED37") (pin "P$13") (pinfunction "GND_P$13") (pintype "bidirectional"))
      (node (ref "LED37") (pin "P$14") (pinfunction "GND_P$14") (pintype "bidirectional"))
      (node (ref "LED37") (pin "P$15") (pinfunction "GND_P$15") (pintype "bidirectional"))
      (node (ref "LED37") (pin "P$3") (pinfunction "GND_P$3") (pintype "bidirectional"))
      (node (ref "LED37") (pin "P$5") (pinfunction "GND_P$5") (pintype "bidirectional"))
      (node (ref "LED37") (pin "P$6") (pinfunction "GND_P$6") (pintype "bidirectional"))
      (node (ref "LED37") (pin "P$7") (pinfunction "GND_P$7") (pintype "bidirectional"))
      (node (ref "LED37") (pin "P$8") (pinfunction "GND_P$8") (pintype "bidirectional"))
      (node (ref "LED37") (pin "P$9") (pinfunction "GND_P$9") (pintype "bidirectional"))
      (node (ref "LED38") (pin "GND") (pinfunction "GND_GND") (pintype "bidirectional"))
      (node (ref "LED38") (pin "P$1") (pinfunction "GND_P$1") (pintype "bidirectional"))
      (node (ref "LED38") (pin "P$11") (pinfunction "GND_P$11") (pintype "bidirectional"))
      (node (ref "LED38") (pin "P$12") (pinfunction "GND_P$12") (pintype "bidirectional"))
      (node (ref "LED38") (pin "P$13") (pinfunction "GND_P$13") (pintype "bidirectional"))
      (node (ref "LED38") (pin "P$14") (pinfunction "GND_P$14") (pintype "bidirectional"))
      (node (ref "LED38") (pin "P$15") (pinfunction "GND_P$15") (pintype "bidirectional"))
      (node (ref "LED38") (pin "P$3") (pinfunction "GND_P$3") (pintype "bidirectional"))
      (node (ref "LED38") (pin "P$5") (pinfunction "GND_P$5") (pintype "bidirectional"))
      (node (ref "LED38") (pin "P$6") (pinfunction "GND_P$6") (pintype "bidirectional"))
      (node (ref "LED38") (pin "P$7") (pinfunction "GND_P$7") (pintype "bidirectional"))
      (node (ref "LED38") (pin "P$8") (pinfunction "GND_P$8") (pintype "bidirectional"))
      (node (ref "LED38") (pin "P$9") (pinfunction "GND_P$9") (pintype "bidirectional"))
      (node (ref "LED39") (pin "GND") (pinfunction "GND_GND") (pintype "bidirectional"))
      (node (ref "LED39") (pin "P$1") (pinfunction "GND_P$1") (pintype "bidirectional"))
      (node (ref "LED39") (pin "P$11") (pinfunction "GND_P$11") (pintype "bidirectional"))
      (node (ref "LED39") (pin "P$12") (pinfunction "GND_P$12") (pintype "bidirectional"))
      (node (ref "LED39") (pin "P$13") (pinfunction "GND_P$13") (pintype "bidirectional"))
      (node (ref "LED39") (pin "P$14") (pinfunction "GND_P$14") (pintype "bidirectional"))
      (node (ref "LED39") (pin "P$15") (pinfunction "GND_P$15") (pintype "bidirectional"))
      (node (ref "LED39") (pin "P$3") (pinfunction "GND_P$3") (pintype "bidirectional"))
      (node (ref "LED39") (pin "P$5") (pinfunction "GND_P$5") (pintype "bidirectional"))
      (node (ref "LED39") (pin "P$6") (pinfunction "GND_P$6") (pintype "bidirectional"))
      (node (ref "LED39") (pin "P$7") (pinfunction "GND_P$7") (pintype "bidirectional"))
      (node (ref "LED39") (pin "P$8") (pinfunction "GND_P$8") (pintype "bidirectional"))
      (node (ref "LED39") (pin "P$9") (pinfunction "GND_P$9") (pintype "bidirectional"))
      (node (ref "LED4") (pin "GND") (pinfunction "GND_GND") (pintype "bidirectional"))
      (node (ref "LED4") (pin "P$1") (pinfunction "GND_P$1") (pintype "bidirectional"))
      (node (ref "LED4") (pin "P$11") (pinfunction "GND_P$11") (pintype "bidirectional"))
      (node (ref "LED4") (pin "P$12") (pinfunction "GND_P$12") (pintype "bidirectional"))
      (node (ref "LED4") (pin "P$13") (pinfunction "GND_P$13") (pintype "bidirectional"))
      (node (ref "LED4") (pin "P$14") (pinfunction "GND_P$14") (pintype "bidirectional"))
      (node (ref "LED4") (pin "P$15") (pinfunction "GND_P$15") (pintype "bidirectional"))
      (node (ref "LED4") (pin "P$3") (pinfunction "GND_P$3") (pintype "bidirectional"))
      (node (ref "LED4") (pin "P$5") (pinfunction "GND_P$5") (pintype "bidirectional"))
      (node (ref "LED4") (pin "P$6") (pinfunction "GND_P$6") (pintype "bidirectional"))
      (node (ref "LED4") (pin "P$7") (pinfunction "GND_P$7") (pintype "bidirectional"))
      (node (ref "LED4") (pin "P$8") (pinfunction "GND_P$8") (pintype "bidirectional"))
      (node (ref "LED4") (pin "P$9") (pinfunction "GND_P$9") (pintype "bidirectional"))
      (node (ref "LED40") (pin "GND") (pinfunction "GND_GND") (pintype "bidirectional"))
      (node (ref "LED40") (pin "P$1") (pinfunction "GND_P$1") (pintype "bidirectional"))
      (node (ref "LED40") (pin "P$11") (pinfunction "GND_P$11") (pintype "bidirectional"))
      (node (ref "LED40") (pin "P$12") (pinfunction "GND_P$12") (pintype "bidirectional"))
      (node (ref "LED40") (pin "P$13") (pinfunction "GND_P$13") (pintype "bidirectional"))
      (node (ref "LED40") (pin "P$14") (pinfunction "GND_P$14") (pintype "bidirectional"))
      (node (ref "LED40") (pin "P$15") (pinfunction "GND_P$15") (pintype "bidirectional"))
      (node (ref "LED40") (pin "P$3") (pinfunction "GND_P$3") (pintype "bidirectional"))
      (node (ref "LED40") (pin "P$5") (pinfunction "GND_P$5") (pintype "bidirectional"))
      (node (ref "LED40") (pin "P$6") (pinfunction "GND_P$6") (pintype "bidirectional"))
      (node (ref "LED40") (pin "P$7") (pinfunction "GND_P$7") (pintype "bidirectional"))
      (node (ref "LED40") (pin "P$8") (pinfunction "GND_P$8") (pintype "bidirectional"))
      (node (ref "LED40") (pin "P$9") (pinfunction "GND_P$9") (pintype "bidirectional"))
      (node (ref "LED41") (pin "GND") (pinfunction "GND_GND") (pintype "bidirectional"))
      (node (ref "LED41") (pin "P$1") (pinfunction "GND_P$1") (pintype "bidirectional"))
      (node (ref "LED41") (pin "P$11") (pinfunction "GND_P$11") (pintype "bidirectional"))
      (node (ref "LED41") (pin "P$12") (pinfunction "GND_P$12") (pintype "bidirectional"))
      (node (ref "LED41") (pin "P$13") (pinfunction "GND_P$13") (pintype "bidirectional"))
      (node (ref "LED41") (pin "P$14") (pinfunction "GND_P$14") (pintype "bidirectional"))
      (node (ref "LED41") (pin "P$15") (pinfunction "GND_P$15") (pintype "bidirectional"))
      (node (ref "LED41") (pin "P$3") (pinfunction "GND_P$3") (pintype "bidirectional"))
      (node (ref "LED41") (pin "P$5") (pinfunction "GND_P$5") (pintype "bidirectional"))
      (node (ref "LED41") (pin "P$6") (pinfunction "GND_P$6") (pintype "bidirectional"))
      (node (ref "LED41") (pin "P$7") (pinfunction "GND_P$7") (pintype "bidirectional"))
      (node (ref "LED41") (pin "P$8") (pinfunction "GND_P$8") (pintype "bidirectional"))
      (node (ref "LED41") (pin "P$9") (pinfunction "GND_P$9") (pintype "bidirectional"))
      (node (ref "LED42") (pin "GND") (pinfunction "GND_GND") (pintype "bidirectional"))
      (node (ref "LED42") (pin "P$1") (pinfunction "GND_P$1") (pintype "bidirectional"))
      (node (ref "LED42") (pin "P$11") (pinfunction "GND_P$11") (pintype "bidirectional"))
      (node (ref "LED42") (pin "P$12") (pinfunction "GND_P$12") (pintype "bidirectional"))
      (node (ref "LED42") (pin "P$13") (pinfunction "GND_P$13") (pintype "bidirectional"))
      (node (ref "LED42") (pin "P$14") (pinfunction "GND_P$14") (pintype "bidirectional"))
      (node (ref "LED42") (pin "P$15") (pinfunction "GND_P$15") (pintype "bidirectional"))
      (node (ref "LED42") (pin "P$3") (pinfunction "GND_P$3") (pintype "bidirectional"))
      (node (ref "LED42") (pin "P$5") (pinfunction "GND_P$5") (pintype "bidirectional"))
      (node (ref "LED42") (pin "P$6") (pinfunction "GND_P$6") (pintype "bidirectional"))
      (node (ref "LED42") (pin "P$7") (pinfunction "GND_P$7") (pintype "bidirectional"))
      (node (ref "LED42") (pin "P$8") (pinfunction "GND_P$8") (pintype "bidirectional"))
      (node (ref "LED42") (pin "P$9") (pinfunction "GND_P$9") (pintype "bidirectional"))
      (node (ref "LED43") (pin "GND") (pinfunction "GND_GND") (pintype "bidirectional"))
      (node (ref "LED43") (pin "P$1") (pinfunction "GND_P$1") (pintype "bidirectional"))
      (node (ref "LED43") (pin "P$11") (pinfunction "GND_P$11") (pintype "bidirectional"))
      (node (ref "LED43") (pin "P$12") (pinfunction "GND_P$12") (pintype "bidirectional"))
      (node (ref "LED43") (pin "P$13") (pinfunction "GND_P$13") (pintype "bidirectional"))
      (node (ref "LED43") (pin "P$14") (pinfunction "GND_P$14") (pintype "bidirectional"))
      (node (ref "LED43") (pin "P$15") (pinfunction "GND_P$15") (pintype "bidirectional"))
      (node (ref "LED43") (pin "P$3") (pinfunction "GND_P$3") (pintype "bidirectional"))
      (node (ref "LED43") (pin "P$5") (pinfunction "GND_P$5") (pintype "bidirectional"))
      (node (ref "LED43") (pin "P$6") (pinfunction "GND_P$6") (pintype "bidirectional"))
      (node (ref "LED43") (pin "P$7") (pinfunction "GND_P$7") (pintype "bidirectional"))
      (node (ref "LED43") (pin "P$8") (pinfunction "GND_P$8") (pintype "bidirectional"))
      (node (ref "LED43") (pin "P$9") (pinfunction "GND_P$9") (pintype "bidirectional"))
      (node (ref "LED44") (pin "GND") (pinfunction "GND_GND") (pintype "bidirectional"))
      (node (ref "LED44") (pin "P$1") (pinfunction "GND_P$1") (pintype "bidirectional"))
      (node (ref "LED44") (pin "P$11") (pinfunction "GND_P$11") (pintype "bidirectional"))
      (node (ref "LED44") (pin "P$12") (pinfunction "GND_P$12") (pintype "bidirectional"))
      (node (ref "LED44") (pin "P$13") (pinfunction "GND_P$13") (pintype "bidirectional"))
      (node (ref "LED44") (pin "P$14") (pinfunction "GND_P$14") (pintype "bidirectional"))
      (node (ref "LED44") (pin "P$15") (pinfunction "GND_P$15") (pintype "bidirectional"))
      (node (ref "LED44") (pin "P$3") (pinfunction "GND_P$3") (pintype "bidirectional"))
      (node (ref "LED44") (pin "P$5") (pinfunction "GND_P$5") (pintype "bidirectional"))
      (node (ref "LED44") (pin "P$6") (pinfunction "GND_P$6") (pintype "bidirectional"))
      (node (ref "LED44") (pin "P$7") (pinfunction "GND_P$7") (pintype "bidirectional"))
      (node (ref "LED44") (pin "P$8") (pinfunction "GND_P$8") (pintype "bidirectional"))
      (node (ref "LED44") (pin "P$9") (pinfunction "GND_P$9") (pintype "bidirectional"))
      (node (ref "LED45") (pin "GND") (pinfunction "GND_GND") (pintype "bidirectional"))
      (node (ref "LED45") (pin "P$1") (pinfunction "GND_P$1") (pintype "bidirectional"))
      (node (ref "LED45") (pin "P$11") (pinfunction "GND_P$11") (pintype "bidirectional"))
      (node (ref "LED45") (pin "P$12") (pinfunction "GND_P$12") (pintype "bidirectional"))
      (node (ref "LED45") (pin "P$13") (pinfunction "GND_P$13") (pintype "bidirectional"))
      (node (ref "LED45") (pin "P$14") (pinfunction "GND_P$14") (pintype "bidirectional"))
      (node (ref "LED45") (pin "P$15") (pinfunction "GND_P$15") (pintype "bidirectional"))
      (node (ref "LED45") (pin "P$3") (pinfunction "GND_P$3") (pintype "bidirectional"))
      (node (ref "LED45") (pin "P$5") (pinfunction "GND_P$5") (pintype "bidirectional"))
      (node (ref "LED45") (pin "P$6") (pinfunction "GND_P$6") (pintype "bidirectional"))
      (node (ref "LED45") (pin "P$7") (pinfunction "GND_P$7") (pintype "bidirectional"))
      (node (ref "LED45") (pin "P$8") (pinfunction "GND_P$8") (pintype "bidirectional"))
      (node (ref "LED45") (pin "P$9") (pinfunction "GND_P$9") (pintype "bidirectional"))
      (node (ref "LED46") (pin "GND") (pinfunction "GND_GND") (pintype "bidirectional"))
      (node (ref "LED46") (pin "P$1") (pinfunction "GND_P$1") (pintype "bidirectional"))
      (node (ref "LED46") (pin "P$11") (pinfunction "GND_P$11") (pintype "bidirectional"))
      (node (ref "LED46") (pin "P$12") (pinfunction "GND_P$12") (pintype "bidirectional"))
      (node (ref "LED46") (pin "P$13") (pinfunction "GND_P$13") (pintype "bidirectional"))
      (node (ref "LED46") (pin "P$14") (pinfunction "GND_P$14") (pintype "bidirectional"))
      (node (ref "LED46") (pin "P$15") (pinfunction "GND_P$15") (pintype "bidirectional"))
      (node (ref "LED46") (pin "P$3") (pinfunction "GND_P$3") (pintype "bidirectional"))
      (node (ref "LED46") (pin "P$5") (pinfunction "GND_P$5") (pintype "bidirectional"))
      (node (ref "LED46") (pin "P$6") (pinfunction "GND_P$6") (pintype "bidirectional"))
      (node (ref "LED46") (pin "P$7") (pinfunction "GND_P$7") (pintype "bidirectional"))
      (node (ref "LED46") (pin "P$8") (pinfunction "GND_P$8") (pintype "bidirectional"))
      (node (ref "LED46") (pin "P$9") (pinfunction "GND_P$9") (pintype "bidirectional"))
      (node (ref "LED47") (pin "GND") (pinfunction "GND_GND") (pintype "bidirectional"))
      (node (ref "LED47") (pin "P$1") (pinfunction "GND_P$1") (pintype "bidirectional"))
      (node (ref "LED47") (pin "P$11") (pinfunction "GND_P$11") (pintype "bidirectional"))
      (node (ref "LED47") (pin "P$12") (pinfunction "GND_P$12") (pintype "bidirectional"))
      (node (ref "LED47") (pin "P$13") (pinfunction "GND_P$13") (pintype "bidirectional"))
      (node (ref "LED47") (pin "P$14") (pinfunction "GND_P$14") (pintype "bidirectional"))
      (node (ref "LED47") (pin "P$15") (pinfunction "GND_P$15") (pintype "bidirectional"))
      (node (ref "LED47") (pin "P$3") (pinfunction "GND_P$3") (pintype "bidirectional"))
      (node (ref "LED47") (pin "P$5") (pinfunction "GND_P$5") (pintype "bidirectional"))
      (node (ref "LED47") (pin "P$6") (pinfunction "GND_P$6") (pintype "bidirectional"))
      (node (ref "LED47") (pin "P$7") (pinfunction "GND_P$7") (pintype "bidirectional"))
      (node (ref "LED47") (pin "P$8") (pinfunction "GND_P$8") (pintype "bidirectional"))
      (node (ref "LED47") (pin "P$9") (pinfunction "GND_P$9") (pintype "bidirectional"))
      (node (ref "LED48") (pin "GND") (pinfunction "GND_GND") (pintype "bidirectional"))
      (node (ref "LED48") (pin "P$1") (pinfunction "GND_P$1") (pintype "bidirectional"))
      (node (ref "LED48") (pin "P$11") (pinfunction "GND_P$11") (pintype "bidirectional"))
      (node (ref "LED48") (pin "P$12") (pinfunction "GND_P$12") (pintype "bidirectional"))
      (node (ref "LED48") (pin "P$13") (pinfunction "GND_P$13") (pintype "bidirectional"))
      (node (ref "LED48") (pin "P$14") (pinfunction "GND_P$14") (pintype "bidirectional"))
      (node (ref "LED48") (pin "P$15") (pinfunction "GND_P$15") (pintype "bidirectional"))
      (node (ref "LED48") (pin "P$3") (pinfunction "GND_P$3") (pintype "bidirectional"))
      (node (ref "LED48") (pin "P$5") (pinfunction "GND_P$5") (pintype "bidirectional"))
      (node (ref "LED48") (pin "P$6") (pinfunction "GND_P$6") (pintype "bidirectional"))
      (node (ref "LED48") (pin "P$7") (pinfunction "GND_P$7") (pintype "bidirectional"))
      (node (ref "LED48") (pin "P$8") (pinfunction "GND_P$8") (pintype "bidirectional"))
      (node (ref "LED48") (pin "P$9") (pinfunction "GND_P$9") (pintype "bidirectional"))
      (node (ref "LED5") (pin "GND") (pinfunction "GND_GND") (pintype "bidirectional"))
      (node (ref "LED5") (pin "P$1") (pinfunction "GND_P$1") (pintype "bidirectional"))
      (node (ref "LED5") (pin "P$11") (pinfunction "GND_P$11") (pintype "bidirectional"))
      (node (ref "LED5") (pin "P$12") (pinfunction "GND_P$12") (pintype "bidirectional"))
      (node (ref "LED5") (pin "P$13") (pinfunction "GND_P$13") (pintype "bidirectional"))
      (node (ref "LED5") (pin "P$14") (pinfunction "GND_P$14") (pintype "bidirectional"))
      (node (ref "LED5") (pin "P$15") (pinfunction "GND_P$15") (pintype "bidirectional"))
      (node (ref "LED5") (pin "P$3") (pinfunction "GND_P$3") (pintype "bidirectional"))
      (node (ref "LED5") (pin "P$5") (pinfunction "GND_P$5") (pintype "bidirectional"))
      (node (ref "LED5") (pin "P$6") (pinfunction "GND_P$6") (pintype "bidirectional"))
      (node (ref "LED5") (pin "P$7") (pinfunction "GND_P$7") (pintype "bidirectional"))
      (node (ref "LED5") (pin "P$8") (pinfunction "GND_P$8") (pintype "bidirectional"))
      (node (ref "LED5") (pin "P$9") (pinfunction "GND_P$9") (pintype "bidirectional"))
      (node (ref "LED6") (pin "GND") (pinfunction "GND_GND") (pintype "bidirectional"))
      (node (ref "LED6") (pin "P$1") (pinfunction "GND_P$1") (pintype "bidirectional"))
      (node (ref "LED6") (pin "P$11") (pinfunction "GND_P$11") (pintype "bidirectional"))
      (node (ref "LED6") (pin "P$12") (pinfunction "GND_P$12") (pintype "bidirectional"))
      (node (ref "LED6") (pin "P$13") (pinfunction "GND_P$13") (pintype "bidirectional"))
      (node (ref "LED6") (pin "P$14") (pinfunction "GND_P$14") (pintype "bidirectional"))
      (node (ref "LED6") (pin "P$15") (pinfunction "GND_P$15") (pintype "bidirectional"))
      (node (ref "LED6") (pin "P$3") (pinfunction "GND_P$3") (pintype "bidirectional"))
      (node (ref "LED6") (pin "P$5") (pinfunction "GND_P$5") (pintype "bidirectional"))
      (node (ref "LED6") (pin "P$6") (pinfunction "GND_P$6") (pintype "bidirectional"))
      (node (ref "LED6") (pin "P$7") (pinfunction "GND_P$7") (pintype "bidirectional"))
      (node (ref "LED6") (pin "P$8") (pinfunction "GND_P$8") (pintype "bidirectional"))
      (node (ref "LED6") (pin "P$9") (pinfunction "GND_P$9") (pintype "bidirectional"))
      (node (ref "LED7") (pin "GND") (pinfunction "GND_GND") (pintype "bidirectional"))
      (node (ref "LED7") (pin "P$1") (pinfunction "GND_P$1") (pintype "bidirectional"))
      (node (ref "LED7") (pin "P$11") (pinfunction "GND_P$11") (pintype "bidirectional"))
      (node (ref "LED7") (pin "P$12") (pinfunction "GND_P$12") (pintype "bidirectional"))
      (node (ref "LED7") (pin "P$13") (pinfunction "GND_P$13") (pintype "bidirectional"))
      (node (ref "LED7") (pin "P$14") (pinfunction "GND_P$14") (pintype "bidirectional"))
      (node (ref "LED7") (pin "P$15") (pinfunction "GND_P$15") (pintype "bidirectional"))
      (node (ref "LED7") (pin "P$3") (pinfunction "GND_P$3") (pintype "bidirectional"))
      (node (ref "LED7") (pin "P$5") (pinfunction "GND_P$5") (pintype "bidirectional"))
      (node (ref "LED7") (pin "P$6") (pinfunction "GND_P$6") (pintype "bidirectional"))
      (node (ref "LED7") (pin "P$7") (pinfunction "GND_P$7") (pintype "bidirectional"))
      (node (ref "LED7") (pin "P$8") (pinfunction "GND_P$8") (pintype "bidirectional"))
      (node (ref "LED7") (pin "P$9") (pinfunction "GND_P$9") (pintype "bidirectional"))
      (node (ref "LED8") (pin "GND") (pinfunction "GND_GND") (pintype "bidirectional"))
      (node (ref "LED8") (pin "P$1") (pinfunction "GND_P$1") (pintype "bidirectional"))
      (node (ref "LED8") (pin "P$11") (pinfunction "GND_P$11") (pintype "bidirectional"))
      (node (ref "LED8") (pin "P$12") (pinfunction "GND_P$12") (pintype "bidirectional"))
      (node (ref "LED8") (pin "P$13") (pinfunction "GND_P$13") (pintype "bidirectional"))
      (node (ref "LED8") (pin "P$14") (pinfunction "GND_P$14") (pintype "bidirectional"))
      (node (ref "LED8") (pin "P$15") (pinfunction "GND_P$15") (pintype "bidirectional"))
      (node (ref "LED8") (pin "P$3") (pinfunction "GND_P$3") (pintype "bidirectional"))
      (node (ref "LED8") (pin "P$5") (pinfunction "GND_P$5") (pintype "bidirectional"))
      (node (ref "LED8") (pin "P$6") (pinfunction "GND_P$6") (pintype "bidirectional"))
      (node (ref "LED8") (pin "P$7") (pinfunction "GND_P$7") (pintype "bidirectional"))
      (node (ref "LED8") (pin "P$8") (pinfunction "GND_P$8") (pintype "bidirectional"))
      (node (ref "LED8") (pin "P$9") (pinfunction "GND_P$9") (pintype "bidirectional"))
      (node (ref "LED9") (pin "GND") (pinfunction "GND_GND") (pintype "bidirectional"))
      (node (ref "LED9") (pin "P$1") (pinfunction "GND_P$1") (pintype "bidirectional"))
      (node (ref "LED9") (pin "P$11") (pinfunction "GND_P$11") (pintype "bidirectional"))
      (node (ref "LED9") (pin "P$12") (pinfunction "GND_P$12") (pintype "bidirectional"))
      (node (ref "LED9") (pin "P$13") (pinfunction "GND_P$13") (pintype "bidirectional"))
      (node (ref "LED9") (pin "P$14") (pinfunction "GND_P$14") (pintype "bidirectional"))
      (node (ref "LED9") (pin "P$15") (pinfunction "GND_P$15") (pintype "bidirectional"))
      (node (ref "LED9") (pin "P$3") (pinfunction "GND_P$3") (pintype "bidirectional"))
      (node (ref "LED9") (pin "P$5") (pinfunction "GND_P$5") (pintype "bidirectional"))
      (node (ref "LED9") (pin "P$6") (pinfunction "GND_P$6") (pintype "bidirectional"))
      (node (ref "LED9") (pin "P$7") (pinfunction "GND_P$7") (pintype "bidirectional"))
      (node (ref "LED9") (pin "P$8") (pinfunction "GND_P$8") (pintype "bidirectional"))
      (node (ref "LED9") (pin "P$9") (pinfunction "GND_P$9") (pintype "bidirectional"))
    )
    (net (code "2") (name "Net-(BLUE+-P)") (class "Default")
      (node (ref "BLUE+") (pin "1") (pinfunction "P_1") (pintype "passive"))
      (node (ref "LED49") (pin "2") (pinfunction "A_2") (pintype "bidirectional"))
      (node (ref "LED53") (pin "2") (pinfunction "A_2") (pintype "bidirectional"))
      (node (ref "LED57") (pin "2") (pinfunction "A_2") (pintype "bidirectional"))
    )
    (net (code "3") (name "Net-(BLUE--P)") (class "Default")
      (node (ref "BLUE-") (pin "1") (pinfunction "P_1") (pintype "passive"))
      (node (ref "LED52") (pin "1") (pinfunction "K_1") (pintype "bidirectional"))
      (node (ref "LED56") (pin "1") (pinfunction "K_1") (pintype "bidirectional"))
      (node (ref "LED60") (pin "1") (pinfunction "K_1") (pintype "bidirectional"))
    )
    (net (code "4") (name "Net-(LED1-A)") (class "Default")
      (node (ref "LED1") (pin "1") (pinfunction "A_1") (pintype "bidirectional"))
      (node (ref "LED19") (pin "1") (pinfunction "A_1") (pintype "bidirectional"))
      (node (ref "RED+") (pin "1") (pinfunction "P_1") (pintype "passive"))
    )
    (net (code "5") (name "Net-(LED1-K)") (class "Default")
      (node (ref "LED1") (pin "2") (pinfunction "K_2") (pintype "bidirectional"))
      (node (ref "LED2") (pin "1") (pinfunction "A_1") (pintype "bidirectional"))
    )
    (net (code "6") (name "Net-(LED2-K)") (class "Default")
      (node (ref "LED2") (pin "2") (pinfunction "K_2") (pintype "bidirectional"))
      (node (ref "LED3") (pin "1") (pinfunction "A_1") (pintype "bidirectional"))
    )
    (net (code "7") (name "Net-(LED3-K)") (class "Default")
      (node (ref "LED3") (pin "2") (pinfunction "K_2") (pintype "bidirectional"))
      (node (ref "LED4") (pin "1") (pinfunction "A_1") (pintype "bidirectional"))
    )
    (net (code "8") (name "Net-(LED4-K)") (class "Default")
      (node (ref "LED4") (pin "2") (pinfunction "K_2") (pintype "bidirectional"))
      (node (ref "LED5") (pin "1") (pinfunction "A_1") (pintype "bidirectional"))
    )
    (net (code "9") (name "Net-(LED5-K)") (class "Default")
      (node (ref "LED5") (pin "2") (pinfunction "K_2") (pintype "bidirectional"))
      (node (ref "LED6") (pin "1") (pinfunction "A_1") (pintype "bidirectional"))
    )
    (net (code "10") (name "Net-(LED6-K)") (class "Default")
      (node (ref "LED6") (pin "2") (pinfunction "K_2") (pintype "bidirectional"))
      (node (ref "LED7") (pin "1") (pinfunction "A_1") (pintype "bidirectional"))
    )
    (net (code "11") (name "Net-(LED7-K)") (class "Default")
      (node (ref "LED7") (pin "2") (pinfunction "K_2") (pintype "bidirectional"))
      (node (ref "LED8") (pin "1") (pinfunction "A_1") (pintype "bidirectional"))
    )
    (net (code "12") (name "Net-(LED8-K)") (class "Default")
      (node (ref "LED8") (pin "2") (pinfunction "K_2") (pintype "bidirectional"))
      (node (ref "LED9") (pin "1") (pinfunction "A_1") (pintype "bidirectional"))
    )
    (net (code "13") (name "Net-(LED10-A)") (class "Default")
      (node (ref "LED10") (pin "1") (pinfunction "A_1") (pintype "bidirectional"))
      (node (ref "LED9") (pin "2") (pinfunction "K_2") (pintype "bidirectional"))
    )
    (net (code "14") (name "Net-(LED10-K)") (class "Default")
      (node (ref "LED10") (pin "2") (pinfunction "K_2") (pintype "bidirectional"))
      (node (ref "LED11") (pin "1") (pinfunction "A_1") (pintype "bidirectional"))
    )
    (net (code "15") (name "Net-(LED11-K)") (class "Default")
      (node (ref "LED11") (pin "2") (pinfunction "K_2") (pintype "bidirectional"))
      (node (ref "LED12") (pin "1") (pinfunction "A_1") (pintype "bidirectional"))
    )
    (net (code "16") (name "Net-(LED12-K)") (class "Default")
      (node (ref "LED12") (pin "2") (pinfunction "K_2") (pintype "bidirectional"))
      (node (ref "LED13") (pin "1") (pinfunction "A_1") (pintype "bidirectional"))
    )
    (net (code "17") (name "Net-(LED13-K)") (class "Default")
      (node (ref "LED13") (pin "2") (pinfunction "K_2") (pintype "bidirectional"))
      (node (ref "LED14") (pin "1") (pinfunction "A_1") (pintype "bidirectional"))
    )
    (net (code "18") (name "Net-(LED14-K)") (class "Default")
      (node (ref "LED14") (pin "2") (pinfunction "K_2") (pintype "bidirectional"))
      (node (ref "LED15") (pin "1") (pinfunction "A_1") (pintype "bidirectional"))
    )
    (net (code "19") (name "Net-(LED15-K)") (class "Default")
      (node (ref "LED15") (pin "2") (pinfunction "K_2") (pintype "bidirectional"))
      (node (ref "LED16") (pin "1") (pinfunction "A_1") (pintype "bidirectional"))
    )
    (net (code "20") (name "Net-(LED16-K)") (class "Default")
      (node (ref "LED16") (pin "2") (pinfunction "K_2") (pintype "bidirectional"))
      (node (ref "LED17") (pin "1") (pinfunction "A_1") (pintype "bidirectional"))
    )
    (net (code "21") (name "Net-(LED17-K)") (class "Default")
      (node (ref "LED17") (pin "2") (pinfunction "K_2") (pintype "bidirectional"))
      (node (ref "LED18") (pin "1") (pinfunction "A_1") (pintype "bidirectional"))
    )
    (net (code "22") (name "Net-(LED18-K)") (class "Default")
      (node (ref "LED18") (pin "2") (pinfunction "K_2") (pintype "bidirectional"))
      (node (ref "LED36") (pin "2") (pinfunction "K_2") (pintype "bidirectional"))
      (node (ref "RED-") (pin "1") (pinfunction "P_1") (pintype "passive"))
    )
    (net (code "23") (name "Net-(LED19-K)") (class "Default")
      (node (ref "LED19") (pin "2") (pinfunction "K_2") (pintype "bidirectional"))
      (node (ref "LED20") (pin "1") (pinfunction "A_1") (pintype "bidirectional"))
    )
    (net (code "24") (name "Net-(LED20-K)") (class "Default")
      (node (ref "LED20") (pin "2") (pinfunction "K_2") (pintype "bidirectional"))
      (node (ref "LED21") (pin "1") (pinfunction "A_1") (pintype "bidirectional"))
    )
    (net (code "25") (name "Net-(LED21-K)") (class "Default")
      (node (ref "LED21") (pin "2") (pinfunction "K_2") (pintype "bidirectional"))
      (node (ref "LED22") (pin "1") (pinfunction "A_1") (pintype "bidirectional"))
    )
    (net (code "26") (name "Net-(LED22-K)") (class "Default")
      (node (ref "LED22") (pin "2") (pinfunction "K_2") (pintype "bidirectional"))
      (node (ref "LED23") (pin "1") (pinfunction "A_1") (pintype "bidirectional"))
    )
    (net (code "27") (name "Net-(LED23-K)") (class "Default")
      (node (ref "LED23") (pin "2") (pinfunction "K_2") (pintype "bidirectional"))
      (node (ref "LED24") (pin "1") (pinfunction "A_1") (pintype "bidirectional"))
    )
    (net (code "28") (name "Net-(LED24-K)") (class "Default")
      (node (ref "LED24") (pin "2") (pinfunction "K_2") (pintype "bidirectional"))
      (node (ref "LED25") (pin "1") (pinfunction "A_1") (pintype "bidirectional"))
    )
    (net (code "29") (name "Net-(LED25-K)") (class "Default")
      (node (ref "LED25") (pin "2") (pinfunction "K_2") (pintype "bidirectional"))
      (node (ref "LED26") (pin "1") (pinfunction "A_1") (pintype "bidirectional"))
    )
    (net (code "30") (name "Net-(LED26-K)") (class "Default")
      (node (ref "LED26") (pin "2") (pinfunction "K_2") (pintype "bidirectional"))
      (node (ref "LED27") (pin "1") (pinfunction "A_1") (pintype "bidirectional"))
    )
    (net (code "31") (name "Net-(LED27-K)") (class "Default")
      (node (ref "LED27") (pin "2") (pinfunction "K_2") (pintype "bidirectional"))
      (node (ref "LED28") (pin "1") (pinfunction "A_1") (pintype "bidirectional"))
    )
    (net (code "32") (name "Net-(LED28-K)") (class "Default")
      (node (ref "LED28") (pin "2") (pinfunction "K_2") (pintype "bidirectional"))
      (node (ref "LED29") (pin "1") (pinfunction "A_1") (pintype "bidirectional"))
    )
    (net (code "33") (name "Net-(LED29-K)") (class "Default")
      (node (ref "LED29") (pin "2") (pinfunction "K_2") (pintype "bidirectional"))
      (node (ref "LED30") (pin "1") (pinfunction "A_1") (pintype "bidirectional"))
    )
    (net (code "34") (name "Net-(LED30-K)") (class "Default")
      (node (ref "LED30") (pin "2") (pinfunction "K_2") (pintype "bidirectional"))
      (node (ref "LED31") (pin "1") (pinfunction "A_1") (pintype "bidirectional"))
    )
    (net (code "35") (name "Net-(LED31-K)") (class "Default")
      (node (ref "LED31") (pin "2") (pinfunction "K_2") (pintype "bidirectional"))
      (node (ref "LED32") (pin "1") (pinfunction "A_1") (pintype "bidirectional"))
    )
    (net (code "36") (name "Net-(LED32-K)") (class "Default")
      (node (ref "LED32") (pin "2") (pinfunction "K_2") (pintype "bidirectional"))
      (node (ref "LED33") (pin "1") (pinfunction "A_1") (pintype "bidirectional"))
    )
    (net (code "37") (name "Net-(LED33-K)") (class "Default")
      (node (ref "LED33") (pin "2") (pinfunction "K_2") (pintype "bidirectional"))
      (node (ref "LED34") (pin "1") (pinfunction "A_1") (pintype "bidirectional"))
    )
    (net (code "38") (name "Net-(LED34-K)") (class "Default")
      (node (ref "LED34") (pin "2") (pinfunction "K_2") (pintype "bidirectional"))
      (node (ref "LED35") (pin "1") (pinfunction "A_1") (pintype "bidirectional"))
    )
    (net (code "39") (name "Net-(LED35-K)") (class "Default")
      (node (ref "LED35") (pin "2") (pinfunction "K_2") (pintype "bidirectional"))
      (node (ref "LED36") (pin "1") (pinfunction "A_1") (pintype "bidirectional"))
    )
    (net (code "40") (name "Net-(LED37-A)") (class "Default")
      (node (ref "LED37") (pin "1") (pinfunction "A_1") (pintype "bidirectional"))
      (node (ref "WHITE+") (pin "1") (pinfunction "P_1") (pintype "passive"))
    )
    (net (code "41") (name "Net-(LED37-K)") (class "Default")
      (node (ref "LED37") (pin "2") (pinfunction "K_2") (pintype "bidirectional"))
      (node (ref "LED38") (pin "1") (pinfunction "A_1") (pintype "bidirectional"))
    )
    (net (code "42") (name "Net-(LED38-K)") (class "Default")
      (node (ref "LED38") (pin "2") (pinfunction "K_2") (pintype "bidirectional"))
      (node (ref "LED39") (pin "1") (pinfunction "A_1") (pintype "bidirectional"))
    )
    (net (code "43") (name "Net-(LED39-K)") (class "Default")
      (node (ref "LED39") (pin "2") (pinfunction "K_2") (pintype "bidirectional"))
      (node (ref "LED40") (pin "1") (pinfunction "A_1") (pintype "bidirectional"))
    )
    (net (code "44") (name "Net-(LED40-K)") (class "Default")
      (node (ref "LED40") (pin "2") (pinfunction "K_2") (pintype "bidirectional"))
      (node (ref "LED41") (pin "1") (pinfunction "A_1") (pintype "bidirectional"))
    )
    (net (code "45") (name "Net-(LED41-K)") (class "Default")
      (node (ref "LED41") (pin "2") (pinfunction "K_2") (pintype "bidirectional"))
      (node (ref "LED42") (pin "1") (pinfunction "A_1") (pintype "bidirectional"))
    )
    (net (code "46") (name "Net-(LED42-K)") (class "Default")
      (node (ref "LED42") (pin "2") (pinfunction "K_2") (pintype "bidirectional"))
      (node (ref "LED43") (pin "1") (pinfunction "A_1") (pintype "bidirectional"))
    )
    (net (code "47") (name "Net-(LED43-K)") (class "Default")
      (node (ref "LED43") (pin "2") (pinfunction "K_2") (pintype "bidirectional"))
      (node (ref "LED44") (pin "1") (pinfunction "A_1") (pintype "bidirectional"))
    )
    (net (code "48") (name "Net-(LED44-K)") (class "Default")
      (node (ref "LED44") (pin "2") (pinfunction "K_2") (pintype "bidirectional"))
      (node (ref "LED45") (pin "1") (pinfunction "A_1") (pintype "bidirectional"))
    )
    (net (code "49") (name "Net-(LED45-K)") (class "Default")
      (node (ref "LED45") (pin "2") (pinfunction "K_2") (pintype "bidirectional"))
      (node (ref "LED46") (pin "1") (pinfunction "A_1") (pintype "bidirectional"))
    )
    (net (code "50") (name "Net-(LED46-K)") (class "Default")
      (node (ref "LED46") (pin "2") (pinfunction "K_2") (pintype "bidirectional"))
      (node (ref "LED47") (pin "1") (pinfunction "A_1") (pintype "bidirectional"))
    )
    (net (code "51") (name "Net-(LED47-K)") (class "Default")
      (node (ref "LED47") (pin "2") (pinfunction "K_2") (pintype "bidirectional"))
      (node (ref "LED48") (pin "1") (pinfunction "A_1") (pintype "bidirectional"))
    )
    (net (code "52") (name "Net-(LED48-K)") (class "Default")
      (node (ref "LED48") (pin "2") (pinfunction "K_2") (pintype "bidirectional"))
      (node (ref "WHITE-") (pin "1") (pinfunction "P_1") (pintype "passive"))
    )
    (net (code "53") (name "Net-(LED49-K)") (class "Default")
      (node (ref "LED49") (pin "1") (pinfunction "K_1") (pintype "bidirectional"))
      (node (ref "LED50") (pin "2") (pinfunction "A_2") (pintype "bidirectional"))
    )
    (net (code "54") (name "Net-(LED50-K)") (class "Default")
      (node (ref "LED50") (pin "1") (pinfunction "K_1") (pintype "bidirectional"))
      (node (ref "LED51") (pin "2") (pinfunction "A_2") (pintype "bidirectional"))
    )
    (net (code "55") (name "Net-(LED51-K)") (class "Default")
      (node (ref "LED51") (pin "1") (pinfunction "K_1") (pintype "bidirectional"))
      (node (ref "LED52") (pin "2") (pinfunction "A_2") (pintype "bidirectional"))
    )
    (net (code "56") (name "Net-(LED53-K)") (class "Default")
      (node (ref "LED53") (pin "1") (pinfunction "K_1") (pintype "bidirectional"))
      (node (ref "LED54") (pin "2") (pinfunction "A_2") (pintype "bidirectional"))
    )
    (net (code "57") (name "Net-(LED54-K)") (class "Default")
      (node (ref "LED54") (pin "1") (pinfunction "K_1") (pintype "bidirectional"))
      (node (ref "LED55") (pin "2") (pinfunction "A_2") (pintype "bidirectional"))
    )
    (net (code "58") (name "Net-(LED55-K)") (class "Default")
      (node (ref "LED55") (pin "1") (pinfunction "K_1") (pintype "bidirectional"))
      (node (ref "LED56") (pin "2") (pinfunction "A_2") (pintype "bidirectional"))
    )
    (net (code "59") (name "Net-(LED57-K)") (class "Default")
      (node (ref "LED57") (pin "1") (pinfunction "K_1") (pintype "bidirectional"))
      (node (ref "LED58") (pin "2") (pinfunction "A_2") (pintype "bidirectional"))
    )
    (net (code "60") (name "Net-(LED58-K)") (class "Default")
      (node (ref "LED58") (pin "1") (pinfunction "K_1") (pintype "bidirectional"))
      (node (ref "LED59") (pin "2") (pinfunction "A_2") (pintype "bidirectional"))
    )
    (net (code "61") (name "Net-(LED59-K)") (class "Default")
      (node (ref "LED59") (pin "1") (pinfunction "K_1") (pintype "bidirectional"))
      (node (ref "LED60") (pin "2") (pinfunction "A_2") (pintype "bidirectional"))
    )
  )
)
